# Calliope_mini_rev2_1.net
KiCad netlist of a schematic drawn in EAGLE
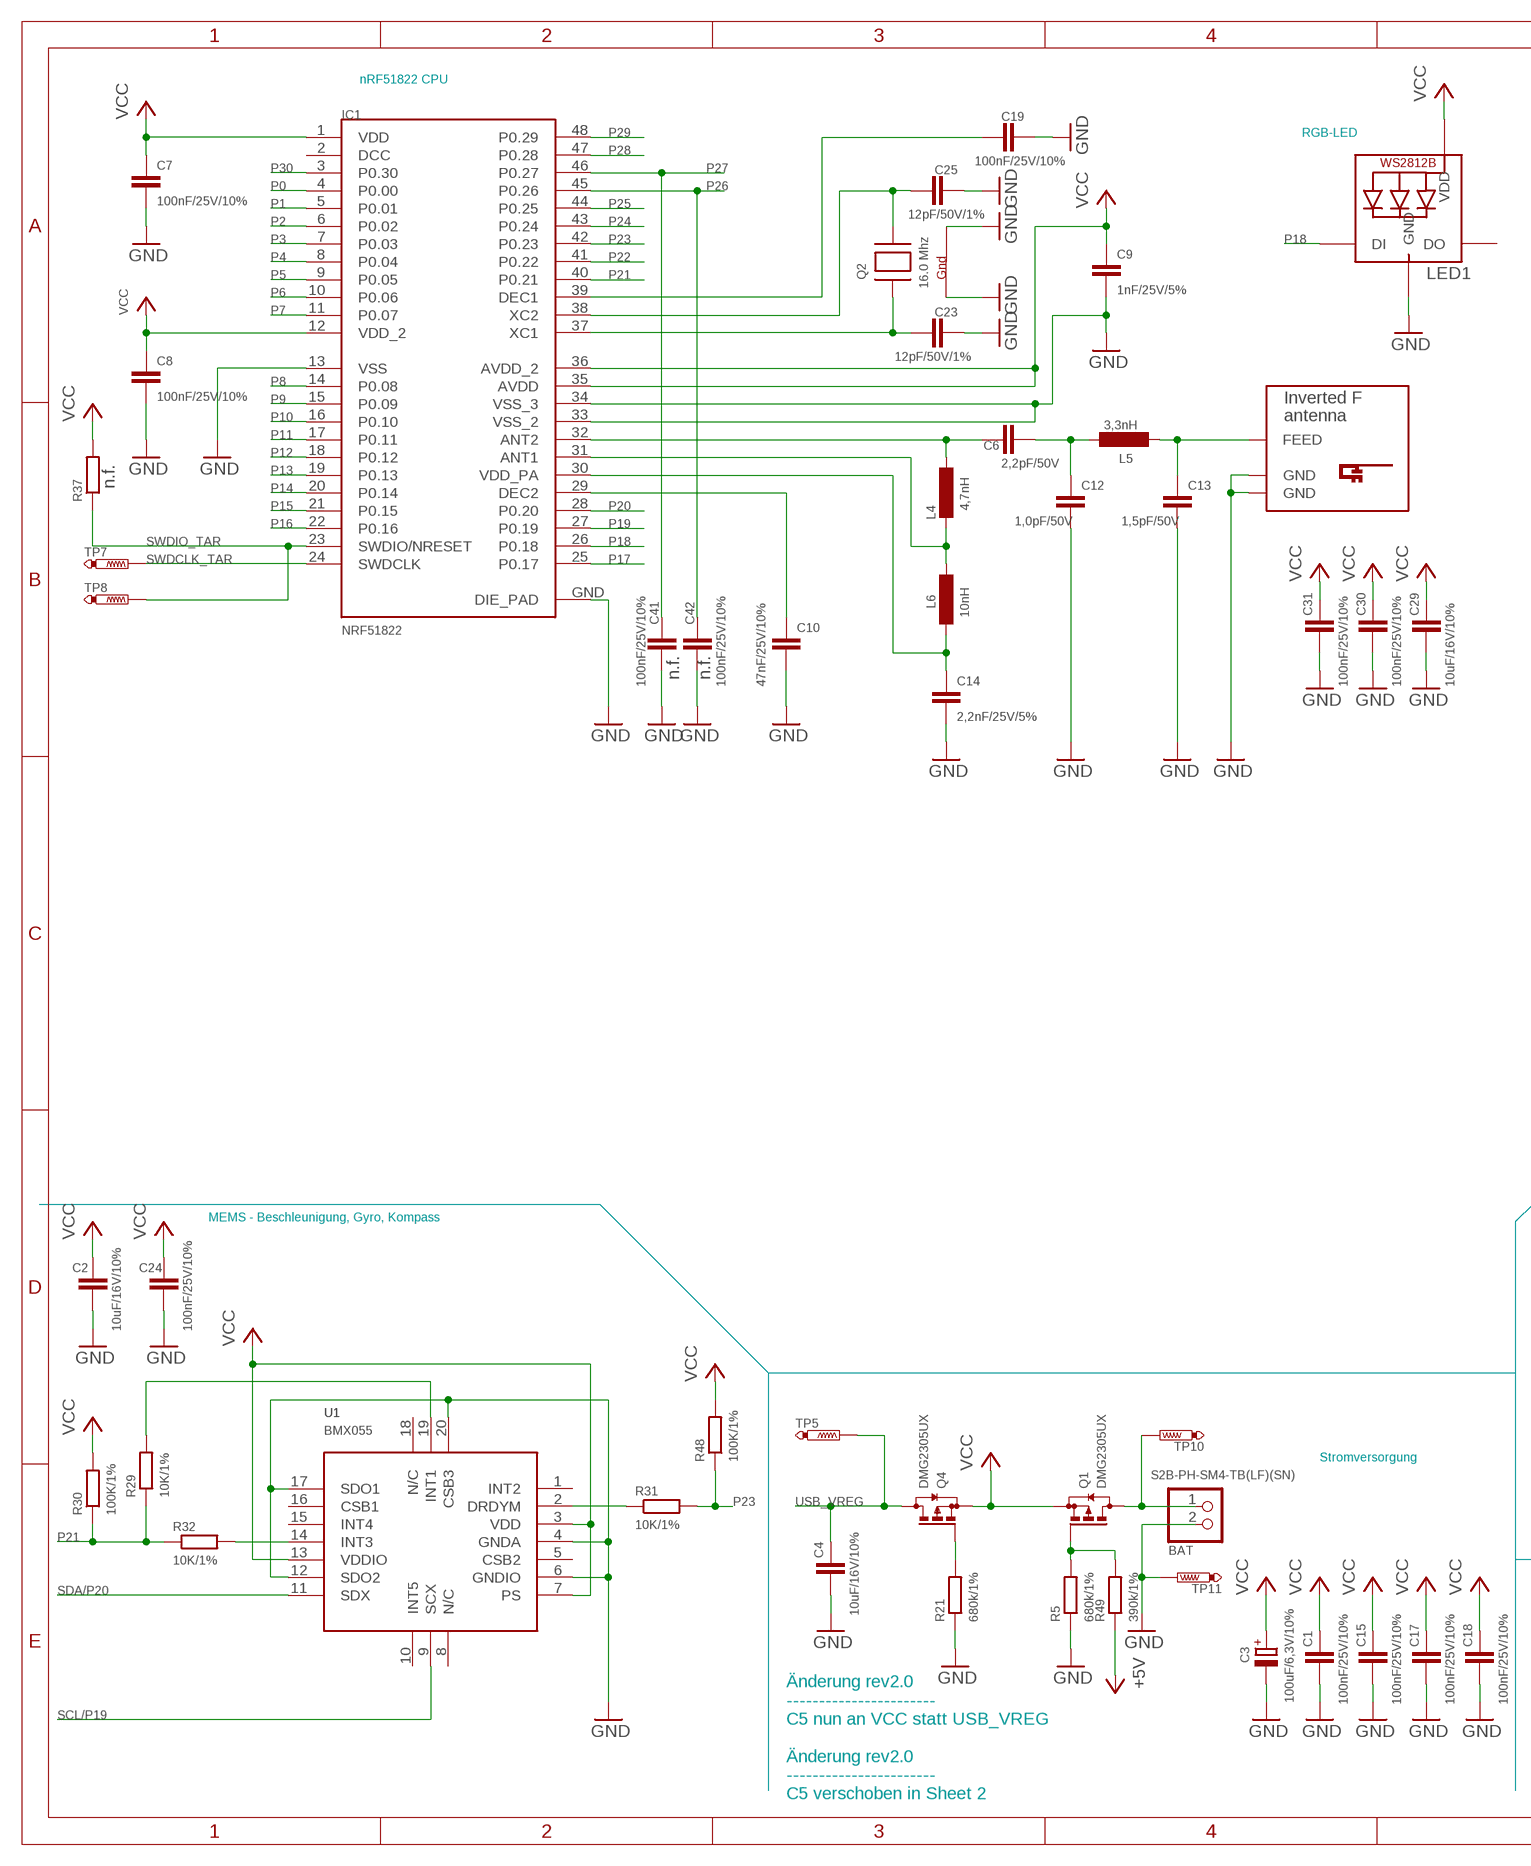
[diagram p0: schematic, sheet 1, part 1 of 2]
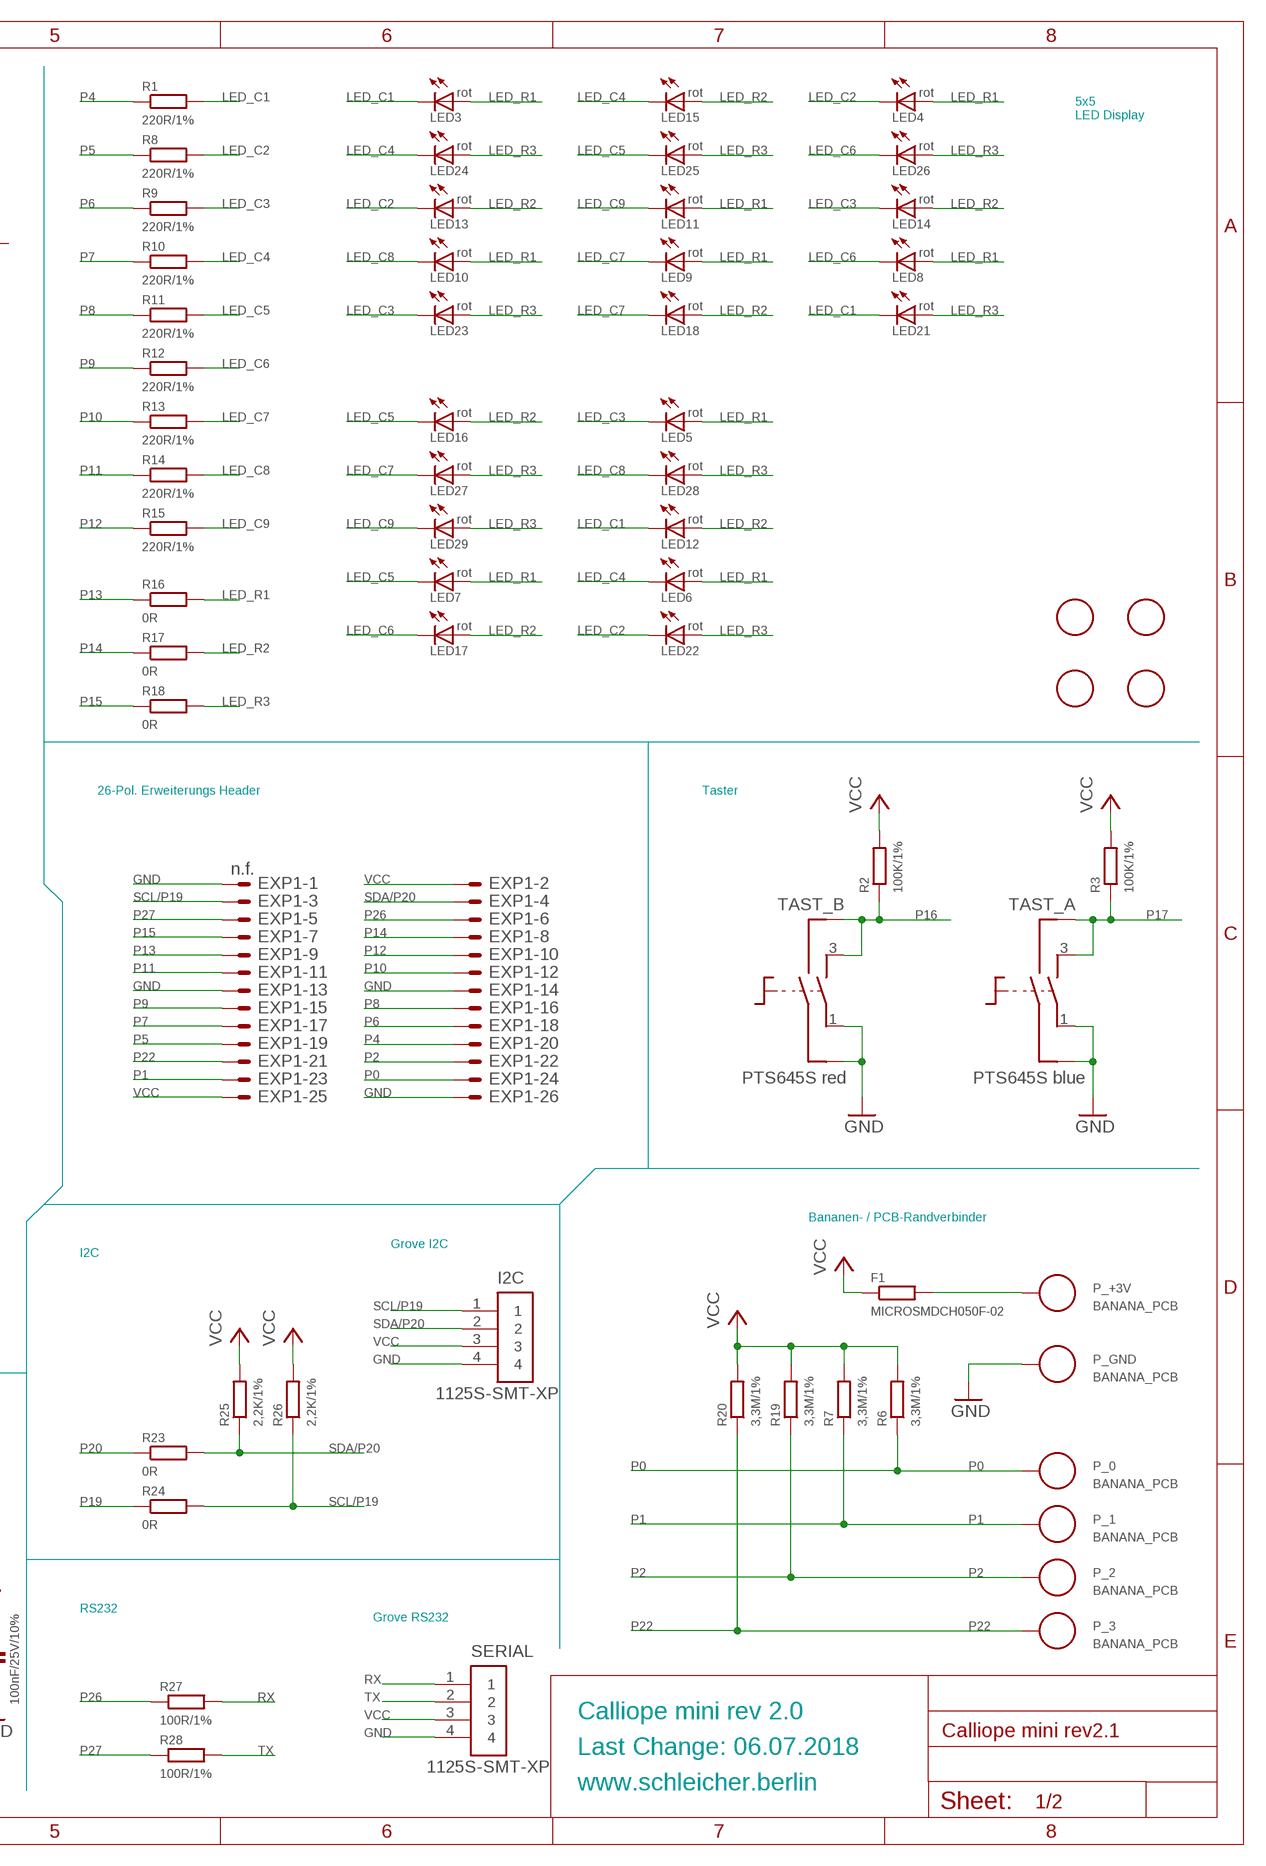
[diagram p1: schematic, sheet 1, part 2 of 2]
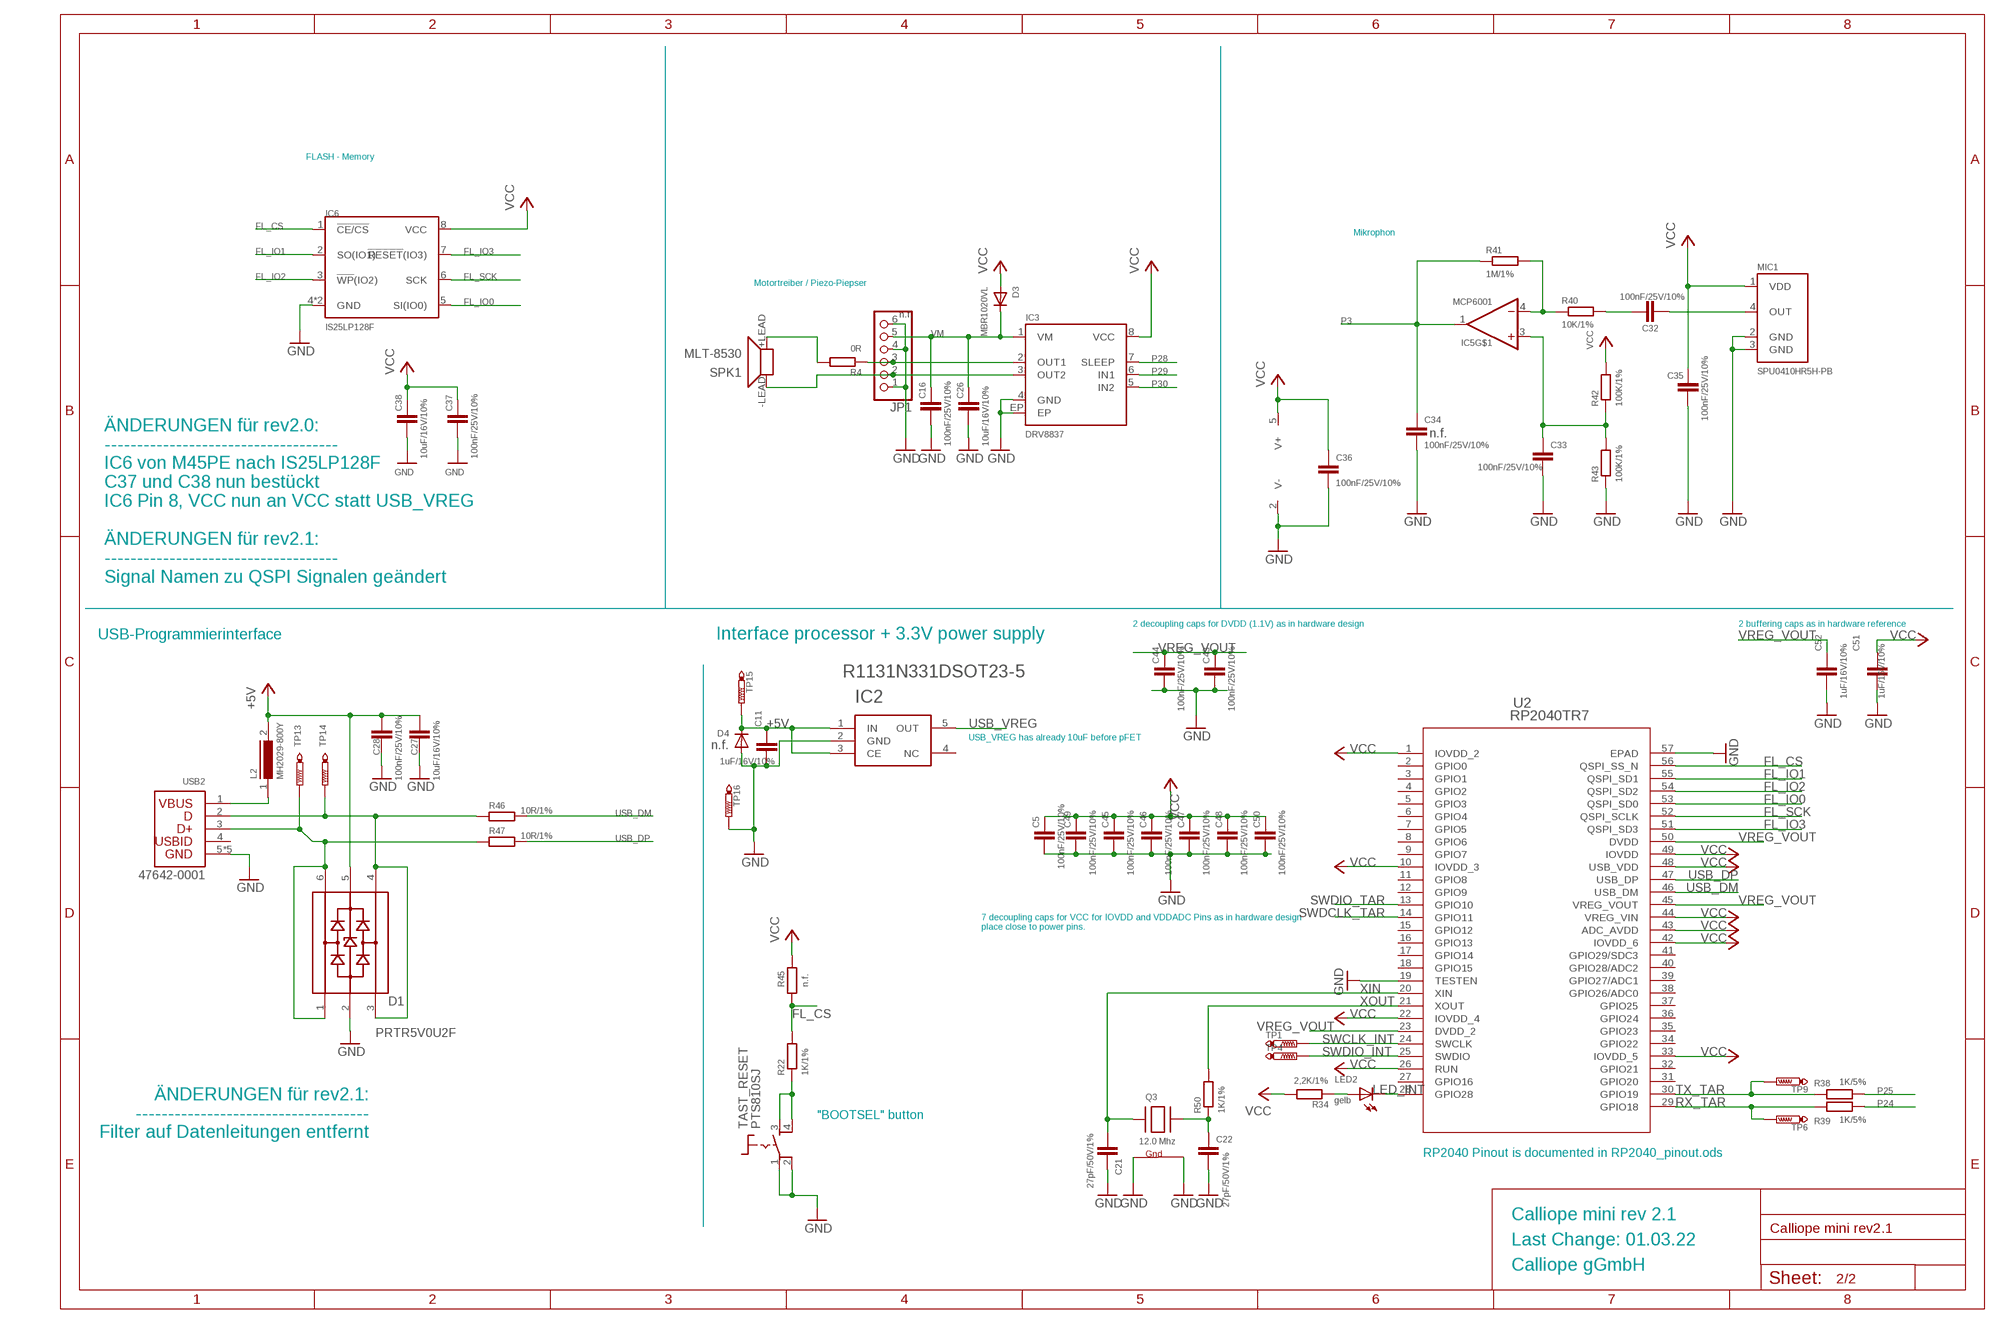
[diagram p2: schematic, sheet 2]

(export (version "E")
  (design (tool "Eeschema 10.0.6"))
  (components
    (comp (ref "C5")
      (value "100nF/25V/10%")
      (footprint "eagle-import:0402")
      (libsource (lib "eagle-import") (part "C-EU0402"))
    )
    (comp (ref "C11")
      (value "1uF/16V/10%")
      (footprint "eagle-import:0402")
      (libsource (lib "eagle-import") (part "rcl_334_C-EU0402"))
    )
    (comp (ref "C16")
      (value "100nF/25V/10%")
      (footprint "eagle-import:0402")
      (libsource (lib "eagle-import") (part "C-EU0402"))
    )
    (comp (ref "C21")
      (value "27pF/50V/1%")
      (footprint "eagle-import:0402")
      (libsource (lib "eagle-import") (part "C-EU0402"))
    )
    (comp (ref "C22")
      (value "27pF/50V/1%")
      (footprint "eagle-import:0402")
      (libsource (lib "eagle-import") (part "C-EU0402"))
    )
    (comp (ref "C26")
      (value "10uF/16V/10%")
      (footprint "eagle-import:0402")
      (libsource (lib "eagle-import") (part "rcl_334_C-EU0402"))
    )
    (comp (ref "C27")
      (value "10uF/16V/10%")
      (footprint "eagle-import:0402")
      (libsource (lib "eagle-import") (part "rcl_334_C-EU0402"))
    )
    (comp (ref "C28")
      (value "100nF/25V/10%")
      (footprint "eagle-import:0402")
      (libsource (lib "eagle-import") (part "C-EU0402"))
    )
    (comp (ref "C32")
      (value "100nF/25V/10%")
      (footprint "eagle-import:0402")
      (libsource (lib "eagle-import") (part "C-EU0402"))
    )
    (comp (ref "C33")
      (value "100nF/25V/10%")
      (footprint "eagle-import:0402")
      (libsource (lib "eagle-import") (part "C-EU0402"))
    )
    (comp (ref "C34")
      (value "100nF/25V/10%")
      (footprint "eagle-import:0402")
      (fields (field (name "MOUNTING") "n.f."))
      (libsource (lib "eagle-import") (part "C-EU0402"))
    )
    (comp (ref "C35")
      (value "100nF/25V/10%")
      (footprint "eagle-import:0402")
      (libsource (lib "eagle-import") (part "C-EU0402"))
    )
    (comp (ref "C36")
      (value "100nF/25V/10%")
      (footprint "eagle-import:0402")
      (libsource (lib "eagle-import") (part "C-EU0402"))
    )
    (comp (ref "C37")
      (value "100nF/25V/10%")
      (footprint "eagle-import:0402")
      (libsource (lib "eagle-import") (part "C-EU0402"))
    )
    (comp (ref "C38")
      (value "10uF/16V/10%")
      (footprint "eagle-import:0402")
      (libsource (lib "eagle-import") (part "rcl_334_C-EU0402"))
    )
    (comp (ref "C43")
      (value "100nF/25V/10%")
      (footprint "eagle-import:0402")
      (libsource (lib "eagle-import") (part "C-EU0402"))
    )
    (comp (ref "C44")
      (value "100nF/25V/10%")
      (footprint "eagle-import:0402")
      (libsource (lib "eagle-import") (part "C-EU0402"))
    )
    (comp (ref "C45")
      (value "100nF/25V/10%")
      (footprint "eagle-import:0402")
      (libsource (lib "eagle-import") (part "C-EU0402"))
    )
    (comp (ref "C46")
      (value "100nF/25V/10%")
      (footprint "eagle-import:0402")
      (libsource (lib "eagle-import") (part "C-EU0402"))
    )
    (comp (ref "C47")
      (value "100nF/25V/10%")
      (footprint "eagle-import:0402")
      (libsource (lib "eagle-import") (part "C-EU0402"))
    )
    (comp (ref "C48")
      (value "100nF/25V/10%")
      (footprint "eagle-import:0402")
      (libsource (lib "eagle-import") (part "C-EU0402"))
    )
    (comp (ref "C49")
      (value "100nF/25V/10%")
      (footprint "eagle-import:0402")
      (libsource (lib "eagle-import") (part "C-EU0402"))
    )
    (comp (ref "C50")
      (value "100nF/25V/10%")
      (footprint "eagle-import:0402")
      (libsource (lib "eagle-import") (part "C-EU0402"))
    )
    (comp (ref "C51")
      (value "1uF/16V/10%")
      (footprint "eagle-import:0402")
      (libsource (lib "eagle-import") (part "rcl_334_C-EU0402"))
    )
    (comp (ref "C52")
      (value "1uF/16V/10%")
      (footprint "eagle-import:0402")
      (libsource (lib "eagle-import") (part "rcl_334_C-EU0402"))
    )
    (comp (ref "D1")
      (value "PRTR5V0U2F")
      (footprint "eagle-import:SOT886")
      (libsource (lib "eagle-import") (part "PRTR5V0U2F"))
    )
    (comp (ref "D3")
      (value "MBR1020VL")
      (footprint "eagle-import:SOD-123FL")
      (libsource (lib "eagle-import") (part "DIODE_SOD-123FL"))
    )
    (comp (ref "D4")
      (value "DIODE-SOD323-R")
      (footprint "eagle-import:SOD323-R")
      (fields (field (name "MOUNTING") "n.f."))
      (libsource (lib "eagle-import") (part "DIODE-SOD323-R"))
    )
    (comp (ref "IC2")
      (value "R1131N331DSOT23-5")
      (footprint "eagle-import:SOT23-5")
      (libsource (lib "eagle-import") (part "R1131N331DSOT23-5"))
    )
    (comp (ref "IC3")
      (value "DRV8837")
      (footprint "eagle-import:WSON8")
      (libsource (lib "eagle-import") (part "DRV8837"))
    )
    (comp (ref "IC5")
      (value "MCP6001")
      (footprint "eagle-import:SOT23-5")
      (libsource (lib "eagle-import") (part "OPAMP_SINGLESOT23-5"))
    )
    (comp (ref "IC6")
      (value "IS25LP128F")
      (footprint "eagle-import:VQFN8_6X5")
      (libsource (lib "eagle-import") (part "IS25LP128F"))
    )
    (comp (ref "JP1")
      (value "PINHD-1X6-OFF")
      (footprint "eagle-import:1X06-OFF")
      (libsource (lib "eagle-import") (part "PINHD-1X6-OFF"))
    )
    (comp (ref "L2")
      (value "MH2029-800Y")
      (footprint "eagle-import:FERRIT_0805")
      (fields (field (name "TOLERANCE") "+-25%"))
      (libsource (lib "eagle-import") (part "MH2029-Y800"))
    )
    (comp (ref "LED2")
      (value "gelb")
      (footprint "eagle-import:CHIPLED_0603")
      (libsource (lib "eagle-import") (part "LEDCHIPLED_0603"))
    )
    (comp (ref "MIC1")
      (value "SPU0410HR5H-PB")
      (footprint "eagle-import:SPU0410HR5H-PB")
      (libsource (lib "eagle-import") (part "SPU0410HR5H-PB"))
    )
    (comp (ref "Q3")
      (value "12.0 Mhz")
      (footprint "eagle-import:NX3225")
      (libsource (lib "eagle-import") (part "XTAL-4-3225"))
    )
    (comp (ref "R4")
      (value "0R")
      (footprint "eagle-import:0402")
      (libsource (lib "eagle-import") (part "R-EU_0402"))
    )
    (comp (ref "R22")
      (value "1K/1%")
      (footprint "eagle-import:0402")
      (libsource (lib "eagle-import") (part "R-EU_0402"))
    )
    (comp (ref "R34")
      (value "2,2K/1%")
      (footprint "eagle-import:0402")
      (libsource (lib "eagle-import") (part "R-EU_0402"))
    )
    (comp (ref "R38")
      (value "1K/5%")
      (footprint "eagle-import:0402")
      (libsource (lib "eagle-import") (part "R-EU_0402"))
    )
    (comp (ref "R39")
      (value "1K/5%")
      (footprint "eagle-import:0402")
      (libsource (lib "eagle-import") (part "R-EU_0402"))
    )
    (comp (ref "R40")
      (value "10K/1%")
      (footprint "eagle-import:0402")
      (libsource (lib "eagle-import") (part "R-EU_0402"))
    )
    (comp (ref "R41")
      (value "1M/1%")
      (footprint "eagle-import:0402")
      (libsource (lib "eagle-import") (part "R-EU_0402"))
    )
    (comp (ref "R42")
      (value "100K/1%")
      (footprint "eagle-import:0402")
      (libsource (lib "eagle-import") (part "R-EU_0402"))
    )
    (comp (ref "R43")
      (value "100K/1%")
      (footprint "eagle-import:0402")
      (libsource (lib "eagle-import") (part "R-EU_0402"))
    )
    (comp (ref "R45")
      (value "n.f.")
      (footprint "eagle-import:0402")
      (libsource (lib "eagle-import") (part "R-EU_0402"))
    )
    (comp (ref "R46")
      (value "10R/1%")
      (footprint "eagle-import:R0402")
      (libsource (lib "eagle-import") (part "rcl_334_R-EU_R0402"))
    )
    (comp (ref "R47")
      (value "10R/1%")
      (footprint "eagle-import:R0402")
      (libsource (lib "eagle-import") (part "rcl_334_R-EU_R0402"))
    )
    (comp (ref "R50")
      (value "1K/1%")
      (footprint "eagle-import:0402")
      (libsource (lib "eagle-import") (part "R-EU_0402"))
    )
    (comp (ref "SPK1")
      (value "MLT-8530")
      (footprint "eagle-import:MLT-8530")
      (libsource (lib "eagle-import") (part "MLT-8530"))
    )
    (comp (ref "TAST_RESET")
      (value "PTS810SJ")
      (footprint "eagle-import:PTS810")
      (libsource (lib "eagle-import") (part "PTS810SJ"))
    )
    (comp (ref "TP1")
      (value "PTR1B1,27")
      (footprint "eagle-import:B1,27")
      (libsource (lib "eagle-import") (part "PTR1B1,27"))
    )
    (comp (ref "TP4")
      (value "PTR1B1,27")
      (footprint "eagle-import:B1,27")
      (libsource (lib "eagle-import") (part "PTR1B1,27"))
    )
    (comp (ref "TP6")
      (value "PTR1B1,27")
      (footprint "eagle-import:B1,27")
      (libsource (lib "eagle-import") (part "PTR1B1,27"))
    )
    (comp (ref "TP9")
      (value "PTR1B1,27")
      (footprint "eagle-import:B1,27")
      (libsource (lib "eagle-import") (part "PTR1B1,27"))
    )
    (comp (ref "TP13")
      (value "PTR1B1,27")
      (footprint "eagle-import:B1,27")
      (libsource (lib "eagle-import") (part "PTR1B1,27"))
    )
    (comp (ref "TP14")
      (value "PTR1B1,27")
      (footprint "eagle-import:B1,27")
      (libsource (lib "eagle-import") (part "PTR1B1,27"))
    )
    (comp (ref "TP15")
      (value "PTR1B1,27")
      (footprint "eagle-import:B1,27")
      (libsource (lib "eagle-import") (part "PTR1B1,27"))
    )
    (comp (ref "TP16")
      (value "PTR1B1,27")
      (footprint "eagle-import:B1,27")
      (libsource (lib "eagle-import") (part "PTR1B1,27"))
    )
    (comp (ref "U2")
      (value "RP2040TR7")
      (footprint "eagle-import:RP2040TR7_RPI")
      (fields (field (name "COPYRIGHT") "Copyright (C) 2022 Ultra Librarian. All rights reserved."))
      (libsource (lib "eagle-import") (part "RP2040TR7"))
    )
    (comp (ref "USB2")
      (value "47642-0001")
      (footprint "eagle-import:47642-0001")
      (libsource (lib "eagle-import") (part "47642-0001"))
    )
    (comp (ref "BAT")
      (value "S2B-PH-SM4-TB(LF)(SN)")
      (footprint "eagle-import:JST-PH-2-SMT-RA")
      (libsource (lib "eagle-import") (part "JST_2PIN-SMT-RA"))
    )
    (comp (ref "C1")
      (value "100nF/25V/10%")
      (footprint "eagle-import:0402")
      (libsource (lib "eagle-import") (part "C-EU0402"))
    )
    (comp (ref "C2")
      (value "10uF/16V/10%")
      (footprint "eagle-import:0402")
      (libsource (lib "eagle-import") (part "rcl_334_C-EU0402"))
    )
    (comp (ref "C3")
      (value "100uF/6,3V/10%")
      (footprint "eagle-import:D_7343-31R")
      (libsource (lib "eagle-import") (part "CPOL-EUD/7343-31R"))
    )
    (comp (ref "C4")
      (value "10uF/16V/10%")
      (footprint "eagle-import:0402")
      (libsource (lib "eagle-import") (part "rcl_334_C-EU0402"))
    )
    (comp (ref "C6")
      (value "2,2pF/50V")
      (footprint "eagle-import:0402")
      (libsource (lib "eagle-import") (part "C-EU0402"))
    )
    (comp (ref "C7")
      (value "100nF/25V/10%")
      (footprint "eagle-import:0402")
      (libsource (lib "eagle-import") (part "C-EU0402"))
    )
    (comp (ref "C8")
      (value "100nF/25V/10%")
      (footprint "eagle-import:0402")
      (libsource (lib "eagle-import") (part "C-EU0402"))
    )
    (comp (ref "C9")
      (value "1nF/25V/5%")
      (footprint "eagle-import:0402")
      (libsource (lib "eagle-import") (part "C-EU0402"))
    )
    (comp (ref "C10")
      (value "47nF/25V/10%")
      (footprint "eagle-import:0402")
      (libsource (lib "eagle-import") (part "C-EU0402"))
    )
    (comp (ref "C12")
      (value "1,0pF/50V")
      (footprint "eagle-import:0402")
      (libsource (lib "eagle-import") (part "C-EU0402"))
    )
    (comp (ref "C13")
      (value "1,5pF/50V")
      (footprint "eagle-import:0402")
      (libsource (lib "eagle-import") (part "C-EU0402"))
    )
    (comp (ref "C14")
      (value "2,2nF/25V/5%")
      (footprint "eagle-import:0402")
      (libsource (lib "eagle-import") (part "C-EU0402"))
    )
    (comp (ref "C15")
      (value "100nF/25V/10%")
      (footprint "eagle-import:0402")
      (libsource (lib "eagle-import") (part "C-EU0402"))
    )
    (comp (ref "C17")
      (value "100nF/25V/10%")
      (footprint "eagle-import:0402")
      (libsource (lib "eagle-import") (part "C-EU0402"))
    )
    (comp (ref "C18")
      (value "100nF/25V/10%")
      (footprint "eagle-import:0402")
      (libsource (lib "eagle-import") (part "C-EU0402"))
    )
    (comp (ref "C19")
      (value "100nF/25V/10%")
      (footprint "eagle-import:0402")
      (libsource (lib "eagle-import") (part "C-EU0402"))
    )
    (comp (ref "C23")
      (value "12pF/50V/1%")
      (footprint "eagle-import:0402")
      (libsource (lib "eagle-import") (part "C-EU0402"))
    )
    (comp (ref "C24")
      (value "100nF/25V/10%")
      (footprint "eagle-import:0402")
      (libsource (lib "eagle-import") (part "C-EU0402"))
    )
    (comp (ref "C25")
      (value "12pF/50V/1%")
      (footprint "eagle-import:0402")
      (libsource (lib "eagle-import") (part "C-EU0402"))
    )
    (comp (ref "C29")
      (value "10uF/16V/10%")
      (footprint "eagle-import:0402")
      (libsource (lib "eagle-import") (part "rcl_334_C-EU0402"))
    )
    (comp (ref "C30")
      (value "100nF/25V/10%")
      (footprint "eagle-import:0402")
      (libsource (lib "eagle-import") (part "C-EU0402"))
    )
    (comp (ref "C31")
      (value "100nF/25V/10%")
      (footprint "eagle-import:0402")
      (libsource (lib "eagle-import") (part "C-EU0402"))
    )
    (comp (ref "C41")
      (value "100nF/25V/10%")
      (footprint "eagle-import:0402")
      (fields (field (name "MOUNTING") "n.f."))
      (libsource (lib "eagle-import") (part "C-EU0402"))
    )
    (comp (ref "C42")
      (value "100nF/25V/10%")
      (footprint "eagle-import:0402")
      (fields (field (name "MOUNTING") "n.f."))
      (libsource (lib "eagle-import") (part "C-EU0402"))
    )
    (comp (ref "EXP1")
      (value "ML26E")
      (footprint "eagle-import:ML26")
      (fields (field (name "MOUNTING") "n.f."))
      (libsource (lib "eagle-import") (part "ML26?E"))
    )
    (comp (ref "F1")
      (value "MICROSMDCH050F-02")
      (footprint "eagle-import:R1210")
      (libsource (lib "eagle-import") (part "R-EU_R1210"))
    )
    (comp (ref "I2C")
      (value "1125S-SMT-XP")
      (footprint "eagle-import:1125S-SMT-XP")
      (libsource (lib "eagle-import") (part "1125-SMT-XPS"))
    )
    (comp (ref "IC1")
      (value "NRF51822")
      (footprint "eagle-import:QFN48")
      (libsource (lib "eagle-import") (part "NRF51822"))
    )
    (comp (ref "L4")
      (value "4,7nH")
      (footprint "eagle-import:0402")
      (libsource (lib "eagle-import") (part "L-EU0402"))
    )
    (comp (ref "L5")
      (value "3,3nH")
      (footprint "eagle-import:0402")
      (libsource (lib "eagle-import") (part "L-EU0402"))
    )
    (comp (ref "L6")
      (value "10nH")
      (footprint "eagle-import:0402")
      (libsource (lib "eagle-import") (part "L-EU0402"))
    )
    (comp (ref "LED1")
      (value "SK6812MINI")
      (footprint "eagle-import:LED3535")
      (libsource (lib "eagle-import") (part "WS2812B3535"))
    )
    (comp (ref "LED3")
      (value "rot")
      (footprint "eagle-import:CHIPLED_0603")
      (libsource (lib "eagle-import") (part "LEDCHIPLED_0603"))
    )
    (comp (ref "LED4")
      (value "rot")
      (footprint "eagle-import:CHIPLED_0603")
      (libsource (lib "eagle-import") (part "LEDCHIPLED_0603"))
    )
    (comp (ref "LED5")
      (value "rot")
      (footprint "eagle-import:CHIPLED_0603")
      (libsource (lib "eagle-import") (part "LEDCHIPLED_0603"))
    )
    (comp (ref "LED6")
      (value "rot")
      (footprint "eagle-import:CHIPLED_0603")
      (libsource (lib "eagle-import") (part "LEDCHIPLED_0603"))
    )
    (comp (ref "LED7")
      (value "rot")
      (footprint "eagle-import:CHIPLED_0603")
      (libsource (lib "eagle-import") (part "LEDCHIPLED_0603"))
    )
    (comp (ref "LED8")
      (value "rot")
      (footprint "eagle-import:CHIPLED_0603")
      (libsource (lib "eagle-import") (part "LEDCHIPLED_0603"))
    )
    (comp (ref "LED9")
      (value "rot")
      (footprint "eagle-import:CHIPLED_0603")
      (libsource (lib "eagle-import") (part "LEDCHIPLED_0603"))
    )
    (comp (ref "LED10")
      (value "rot")
      (footprint "eagle-import:CHIPLED_0603")
      (libsource (lib "eagle-import") (part "LEDCHIPLED_0603"))
    )
    (comp (ref "LED11")
      (value "rot")
      (footprint "eagle-import:CHIPLED_0603")
      (libsource (lib "eagle-import") (part "LEDCHIPLED_0603"))
    )
    (comp (ref "LED12")
      (value "rot")
      (footprint "eagle-import:CHIPLED_0603")
      (libsource (lib "eagle-import") (part "LEDCHIPLED_0603"))
    )
    (comp (ref "LED13")
      (value "rot")
      (footprint "eagle-import:CHIPLED_0603")
      (libsource (lib "eagle-import") (part "LEDCHIPLED_0603"))
    )
    (comp (ref "LED14")
      (value "rot")
      (footprint "eagle-import:CHIPLED_0603")
      (libsource (lib "eagle-import") (part "LEDCHIPLED_0603"))
    )
    (comp (ref "LED15")
      (value "rot")
      (footprint "eagle-import:CHIPLED_0603")
      (libsource (lib "eagle-import") (part "LEDCHIPLED_0603"))
    )
    (comp (ref "LED16")
      (value "rot")
      (footprint "eagle-import:CHIPLED_0603")
      (libsource (lib "eagle-import") (part "LEDCHIPLED_0603"))
    )
    (comp (ref "LED17")
      (value "rot")
      (footprint "eagle-import:CHIPLED_0603")
      (libsource (lib "eagle-import") (part "LEDCHIPLED_0603"))
    )
    (comp (ref "LED18")
      (value "rot")
      (footprint "eagle-import:CHIPLED_0603")
      (libsource (lib "eagle-import") (part "LEDCHIPLED_0603"))
    )
    (comp (ref "LED21")
      (value "rot")
      (footprint "eagle-import:CHIPLED_0603")
      (libsource (lib "eagle-import") (part "LEDCHIPLED_0603"))
    )
    (comp (ref "LED22")
      (value "rot")
      (footprint "eagle-import:CHIPLED_0603")
      (libsource (lib "eagle-import") (part "LEDCHIPLED_0603"))
    )
    (comp (ref "LED23")
      (value "rot")
      (footprint "eagle-import:CHIPLED_0603")
      (libsource (lib "eagle-import") (part "LEDCHIPLED_0603"))
    )
    (comp (ref "LED24")
      (value "rot")
      (footprint "eagle-import:CHIPLED_0603")
      (libsource (lib "eagle-import") (part "LEDCHIPLED_0603"))
    )
    (comp (ref "LED25")
      (value "rot")
      (footprint "eagle-import:CHIPLED_0603")
      (libsource (lib "eagle-import") (part "LEDCHIPLED_0603"))
    )
    (comp (ref "LED26")
      (value "rot")
      (footprint "eagle-import:CHIPLED_0603")
      (libsource (lib "eagle-import") (part "LEDCHIPLED_0603"))
    )
    (comp (ref "LED27")
      (value "rot")
      (footprint "eagle-import:CHIPLED_0603")
      (libsource (lib "eagle-import") (part "LEDCHIPLED_0603"))
    )
    (comp (ref "LED28")
      (value "rot")
      (footprint "eagle-import:CHIPLED_0603")
      (libsource (lib "eagle-import") (part "LEDCHIPLED_0603"))
    )
    (comp (ref "LED29")
      (value "rot")
      (footprint "eagle-import:CHIPLED_0603")
      (libsource (lib "eagle-import") (part "LEDCHIPLED_0603"))
    )
    (comp (ref "P_+3V")
      (value "BANANA_PCB")
      (footprint "eagle-import:BANANA_REC")
      (libsource (lib "eagle-import") (part "BANANA_PCB"))
    )
    (comp (ref "P_0")
      (value "BANANA_PCB")
      (footprint "eagle-import:BANANA_REC")
      (libsource (lib "eagle-import") (part "BANANA_PCB"))
    )
    (comp (ref "P_1")
      (value "BANANA_PCB")
      (footprint "eagle-import:BANANA_REC")
      (libsource (lib "eagle-import") (part "BANANA_PCB"))
    )
    (comp (ref "P_2")
      (value "BANANA_PCB")
      (footprint "eagle-import:BANANA_REC")
      (libsource (lib "eagle-import") (part "BANANA_PCB"))
    )
    (comp (ref "P_3")
      (value "BANANA_PCB")
      (footprint "eagle-import:BANANA_REC")
      (libsource (lib "eagle-import") (part "BANANA_PCB"))
    )
    (comp (ref "P_GND")
      (value "BANANA_PCB")
      (footprint "eagle-import:BANANA_REC")
      (libsource (lib "eagle-import") (part "BANANA_PCB"))
    )
    (comp (ref "Q1")
      (value "DMG2305UX")
      (footprint "eagle-import:SOT23")
      (libsource (lib "eagle-import") (part "BSS84"))
    )
    (comp (ref "Q2")
      (value "16.0 Mhz")
      (footprint "eagle-import:NX3225")
      (libsource (lib "eagle-import") (part "XTAL-4-3225"))
    )
    (comp (ref "Q4")
      (value "DMG2305UX")
      (footprint "eagle-import:SOT23")
      (libsource (lib "eagle-import") (part "BSS84"))
    )
    (comp (ref "R1")
      (value "220R/1%")
      (footprint "eagle-import:0402")
      (libsource (lib "eagle-import") (part "R-EU_0402"))
    )
    (comp (ref "R2")
      (value "100K/1%")
      (footprint "eagle-import:0402")
      (libsource (lib "eagle-import") (part "R-EU_0402"))
    )
    (comp (ref "R3")
      (value "100K/1%")
      (footprint "eagle-import:0402")
      (libsource (lib "eagle-import") (part "R-EU_0402"))
    )
    (comp (ref "R5")
      (value "680k/1%")
      (footprint "eagle-import:0402")
      (libsource (lib "eagle-import") (part "R-EU_0402"))
    )
    (comp (ref "R6")
      (value "3,3M/1%")
      (footprint "eagle-import:0402")
      (libsource (lib "eagle-import") (part "R-EU_0402"))
    )
    (comp (ref "R7")
      (value "3,3M/1%")
      (footprint "eagle-import:0402")
      (libsource (lib "eagle-import") (part "R-EU_0402"))
    )
    (comp (ref "R8")
      (value "220R/1%")
      (footprint "eagle-import:0402")
      (libsource (lib "eagle-import") (part "R-EU_0402"))
    )
    (comp (ref "R9")
      (value "220R/1%")
      (footprint "eagle-import:0402")
      (libsource (lib "eagle-import") (part "R-EU_0402"))
    )
    (comp (ref "R10")
      (value "220R/1%")
      (footprint "eagle-import:0402")
      (libsource (lib "eagle-import") (part "R-EU_0402"))
    )
    (comp (ref "R11")
      (value "220R/1%")
      (footprint "eagle-import:0402")
      (libsource (lib "eagle-import") (part "R-EU_0402"))
    )
    (comp (ref "R12")
      (value "220R/1%")
      (footprint "eagle-import:0402")
      (libsource (lib "eagle-import") (part "R-EU_0402"))
    )
    (comp (ref "R13")
      (value "220R/1%")
      (footprint "eagle-import:0402")
      (libsource (lib "eagle-import") (part "R-EU_0402"))
    )
    (comp (ref "R14")
      (value "220R/1%")
      (footprint "eagle-import:0402")
      (libsource (lib "eagle-import") (part "R-EU_0402"))
    )
    (comp (ref "R15")
      (value "220R/1%")
      (footprint "eagle-import:0402")
      (libsource (lib "eagle-import") (part "R-EU_0402"))
    )
    (comp (ref "R16")
      (value "0R")
      (footprint "eagle-import:0402")
      (libsource (lib "eagle-import") (part "R-EU_0402"))
    )
    (comp (ref "R17")
      (value "0R")
      (footprint "eagle-import:0402")
      (libsource (lib "eagle-import") (part "R-EU_0402"))
    )
    (comp (ref "R18")
      (value "0R")
      (footprint "eagle-import:0402")
      (libsource (lib "eagle-import") (part "R-EU_0402"))
    )
    (comp (ref "R19")
      (value "3,3M/1%")
      (footprint "eagle-import:0402")
      (libsource (lib "eagle-import") (part "R-EU_0402"))
    )
    (comp (ref "R20")
      (value "3,3M/1%")
      (footprint "eagle-import:0402")
      (libsource (lib "eagle-import") (part "R-EU_0402"))
    )
    (comp (ref "R21")
      (value "680k/1%")
      (footprint "eagle-import:0402")
      (libsource (lib "eagle-import") (part "R-EU_0402"))
    )
    (comp (ref "R23")
      (value "0R")
      (footprint "eagle-import:0402")
      (libsource (lib "eagle-import") (part "R-EU_0402"))
    )
    (comp (ref "R24")
      (value "0R")
      (footprint "eagle-import:0402")
      (libsource (lib "eagle-import") (part "R-EU_0402"))
    )
    (comp (ref "R25")
      (value "2,2K/1%")
      (footprint "eagle-import:0402")
      (libsource (lib "eagle-import") (part "R-EU_0402"))
    )
    (comp (ref "R26")
      (value "2,2K/1%")
      (footprint "eagle-import:0402")
      (libsource (lib "eagle-import") (part "R-EU_0402"))
    )
    (comp (ref "R27")
      (value "100R/1%")
      (footprint "eagle-import:0402")
      (libsource (lib "eagle-import") (part "R-EU_0402"))
    )
    (comp (ref "R28")
      (value "100R/1%")
      (footprint "eagle-import:0402")
      (libsource (lib "eagle-import") (part "R-EU_0402"))
    )
    (comp (ref "R29")
      (value "10K/1%")
      (footprint "eagle-import:0402")
      (libsource (lib "eagle-import") (part "R-EU_0402"))
    )
    (comp (ref "R30")
      (value "100K/1%")
      (footprint "eagle-import:0402")
      (libsource (lib "eagle-import") (part "R-EU_0402"))
    )
    (comp (ref "R31")
      (value "10K/1%")
      (footprint "eagle-import:0402")
      (libsource (lib "eagle-import") (part "R-EU_0402"))
    )
    (comp (ref "R32")
      (value "10K/1%")
      (footprint "eagle-import:0402")
      (libsource (lib "eagle-import") (part "R-EU_0402"))
    )
    (comp (ref "R37")
      (value "R-EU_0402")
      (footprint "eagle-import:0402")
      (fields (field (name "MOUNTING") "n.f."))
      (libsource (lib "eagle-import") (part "R-EU_0402"))
    )
    (comp (ref "R48")
      (value "100K/1%")
      (footprint "eagle-import:0402")
      (libsource (lib "eagle-import") (part "R-EU_0402"))
    )
    (comp (ref "R49")
      (value "390k/1%")
      (footprint "eagle-import:0402")
      (libsource (lib "eagle-import") (part "R-EU_0402"))
    )
    (comp (ref "SERIAL")
      (value "1125S-SMT-XP")
      (footprint "eagle-import:1125S-SMT-XP")
      (libsource (lib "eagle-import") (part "1125-SMT-XPS"))
    )
    (comp (ref "TAST_A")
      (value "PTS645S blue")
      (footprint "eagle-import:PTS645S")
      (libsource (lib "eagle-import") (part "PTS645S"))
    )
    (comp (ref "TAST_B")
      (value "PTS645S red")
      (footprint "eagle-import:PTS645S")
      (libsource (lib "eagle-import") (part "PTS645S"))
    )
    (comp (ref "TP5")
      (value "PTR1B1,27")
      (footprint "eagle-import:B1,27")
      (libsource (lib "eagle-import") (part "PTR1B1,27"))
    )
    (comp (ref "TP7")
      (value "PTR1B1,27")
      (footprint "eagle-import:B1,27")
      (libsource (lib "eagle-import") (part "PTR1B1,27"))
    )
    (comp (ref "TP8")
      (value "PTR1B1,27")
      (footprint "eagle-import:B1,27")
      (libsource (lib "eagle-import") (part "PTR1B1,27"))
    )
    (comp (ref "TP10")
      (value "PTR1B1,27")
      (footprint "eagle-import:B1,27")
      (libsource (lib "eagle-import") (part "PTR1B1,27"))
    )
    (comp (ref "TP11")
      (value "PTR1B1,27")
      (footprint "eagle-import:B1,27")
      (libsource (lib "eagle-import") (part "PTR1B1,27"))
    )
    (comp (ref "U$2")
      (value "INVERTED_F_ANTENNA")
      (footprint "eagle-import:DN0007+0_MIRROR")
      (libsource (lib "eagle-import") (part "INVERTED_F_ANTENNA"))
    )
    (comp (ref "U$5")
      (value "FIDUCIAL")
      (footprint "eagle-import:FIDUCIAL_1MM")
      (libsource (lib "eagle-import") (part "FIDUCIAL"))
    )
    (comp (ref "U$6")
      (value "FIDUCIAL")
      (footprint "eagle-import:FIDUCIAL_1MM")
      (libsource (lib "eagle-import") (part "FIDUCIAL"))
    )
    (comp (ref "U$7")
      (value "FIDUCIAL")
      (footprint "eagle-import:FIDUCIAL_1MM")
      (libsource (lib "eagle-import") (part "FIDUCIAL"))
    )
    (comp (ref "U$8")
      (value "FIDUCIAL")
      (footprint "eagle-import:FIDUCIAL_1MM")
      (libsource (lib "eagle-import") (part "FIDUCIAL"))
    )
    (comp (ref "U1")
      (value "BMX055")
      (footprint "eagle-import:BMX055")
      (libsource (lib "eagle-import") (part "BMX055"))
    )
  )
  (nets
    (net (code "1") (name "+5V") (class "Default")
      (node (ref "C11") (pin "1") (pinfunction "1_1") (pintype "passive"))
      (node (ref "C27") (pin "1") (pinfunction "1_1") (pintype "passive"))
      (node (ref "C28") (pin "1") (pinfunction "1_1") (pintype "passive"))
      (node (ref "D1") (pin "5") (pinfunction "5_5") (pintype "bidirectional"))
      (node (ref "D4") (pin "C") (pinfunction "C_C") (pintype "passive"))
      (node (ref "IC2") (pin "1") (pinfunction "IN_1") (pintype "input"))
      (node (ref "IC2") (pin "3") (pinfunction "CE_3") (pintype "input"))
      (node (ref "L2") (pin "2") (pinfunction "2_2") (pintype "passive"))
      (node (ref "R49") (pin "1") (pinfunction "1_1") (pintype "passive"))
      (node (ref "TP15") (pin "TP") (pinfunction "TP_TP") (pintype "input"))
    )
    (net (code "2") (name "FL_CS") (class "Default")
      (node (ref "IC6") (pin "1") (pinfunction "~{CE/CS}_1") (pintype "bidirectional"))
      (node (ref "R22") (pin "2") (pinfunction "2_2") (pintype "passive"))
      (node (ref "R45") (pin "1") (pinfunction "1_1") (pintype "passive"))
      (node (ref "U2") (pin "56") (pinfunction "QSPI_SS_N_56") (pintype "bidirectional"))
    )
    (net (code "3") (name "FL_IO0") (class "Default")
      (node (ref "IC6") (pin "5") (pinfunction "SI(IO0)_5") (pintype "bidirectional"))
      (node (ref "U2") (pin "53") (pinfunction "QSPI_SD0_53") (pintype "bidirectional"))
    )
    (net (code "4") (name "FL_IO1") (class "Default")
      (node (ref "IC6") (pin "2") (pinfunction "SO(IO1)_2") (pintype "bidirectional"))
      (node (ref "U2") (pin "55") (pinfunction "QSPI_SD1_55") (pintype "bidirectional"))
    )
    (net (code "5") (name "FL_IO2") (class "Default")
      (node (ref "IC6") (pin "3") (pinfunction "~{WP}(IO2)_3") (pintype "bidirectional"))
      (node (ref "U2") (pin "54") (pinfunction "QSPI_SD2_54") (pintype "bidirectional"))
    )
    (net (code "6") (name "FL_IO3") (class "Default")
      (node (ref "IC6") (pin "7") (pinfunction "~{RESET}(IO3)_7") (pintype "bidirectional"))
      (node (ref "U2") (pin "51") (pinfunction "QSPI_SD3_51") (pintype "bidirectional"))
    )
    (net (code "7") (name "FL_SCK") (class "Default")
      (node (ref "IC6") (pin "6") (pinfunction "SCK_6") (pintype "bidirectional"))
      (node (ref "U2") (pin "52") (pinfunction "QSPI_SCLK_52") (pintype "bidirectional"))
    )
    (net (code "8") (name "GND") (class "Default")
      (node (ref "BAT") (pin "2") (pinfunction "1_2") (pintype "passive"))
      (node (ref "C1") (pin "2") (pinfunction "2_2") (pintype "passive"))
      (node (ref "C10") (pin "2") (pinfunction "2_2") (pintype "passive"))
      (node (ref "C11") (pin "2") (pinfunction "2_2") (pintype "passive"))
      (node (ref "C12") (pin "2") (pinfunction "2_2") (pintype "passive"))
      (node (ref "C13") (pin "2") (pinfunction "2_2") (pintype "passive"))
      (node (ref "C14") (pin "2") (pinfunction "2_2") (pintype "passive"))
      (node (ref "C15") (pin "2") (pinfunction "2_2") (pintype "passive"))
      (node (ref "C16") (pin "2") (pinfunction "2_2") (pintype "passive"))
      (node (ref "C17") (pin "2") (pinfunction "2_2") (pintype "passive"))
      (node (ref "C18") (pin "2") (pinfunction "2_2") (pintype "passive"))
      (node (ref "C19") (pin "2") (pinfunction "2_2") (pintype "passive"))
      (node (ref "C2") (pin "2") (pinfunction "2_2") (pintype "passive"))
      (node (ref "C21") (pin "2") (pinfunction "2_2") (pintype "passive"))
      (node (ref "C22") (pin "2") (pinfunction "2_2") (pintype "passive"))
      (node (ref "C23") (pin "2") (pinfunction "2_2") (pintype "passive"))
      (node (ref "C24") (pin "2") (pinfunction "2_2") (pintype "passive"))
      (node (ref "C25") (pin "2") (pinfunction "2_2") (pintype "passive"))
      (node (ref "C26") (pin "2") (pinfunction "2_2") (pintype "passive"))
      (node (ref "C27") (pin "2") (pinfunction "2_2") (pintype "passive"))
      (node (ref "C28") (pin "2") (pinfunction "2_2") (pintype "passive"))
      (node (ref "C29") (pin "2") (pinfunction "2_2") (pintype "passive"))
      (node (ref "C3") (pin "-") (pinfunction "-_-") (pintype "passive"))
      (node (ref "C30") (pin "2") (pinfunction "2_2") (pintype "passive"))
      (node (ref "C31") (pin "2") (pinfunction "2_2") (pintype "passive"))
      (node (ref "C33") (pin "2") (pinfunction "2_2") (pintype "passive"))
      (node (ref "C34") (pin "2") (pinfunction "2_2") (pintype "passive"))
      (node (ref "C35") (pin "2") (pinfunction "2_2") (pintype "passive"))
      (node (ref "C36") (pin "2") (pinfunction "2_2") (pintype "passive"))
      (node (ref "C37") (pin "2") (pinfunction "2_2") (pintype "passive"))
      (node (ref "C38") (pin "2") (pinfunction "2_2") (pintype "passive"))
      (node (ref "C4") (pin "2") (pinfunction "2_2") (pintype "passive"))
      (node (ref "C41") (pin "2") (pinfunction "2_2") (pintype "passive"))
      (node (ref "C42") (pin "2") (pinfunction "2_2") (pintype "passive"))
      (node (ref "C43") (pin "2") (pinfunction "2_2") (pintype "passive"))
      (node (ref "C44") (pin "2") (pinfunction "2_2") (pintype "passive"))
      (node (ref "C45") (pin "2") (pinfunction "2_2") (pintype "passive"))
      (node (ref "C46") (pin "2") (pinfunction "2_2") (pintype "passive"))
      (node (ref "C47") (pin "2") (pinfunction "2_2") (pintype "passive"))
      (node (ref "C48") (pin "2") (pinfunction "2_2") (pintype "passive"))
      (node (ref "C49") (pin "2") (pinfunction "2_2") (pintype "passive"))
      (node (ref "C5") (pin "2") (pinfunction "2_2") (pintype "passive"))
      (node (ref "C50") (pin "2") (pinfunction "2_2") (pintype "passive"))
      (node (ref "C51") (pin "2") (pinfunction "2_2") (pintype "passive"))
      (node (ref "C52") (pin "2") (pinfunction "2_2") (pintype "passive"))
      (node (ref "C7") (pin "2") (pinfunction "2_2") (pintype "passive"))
      (node (ref "C8") (pin "2") (pinfunction "2_2") (pintype "passive"))
      (node (ref "C9") (pin "2") (pinfunction "2_2") (pintype "passive"))
      (node (ref "D1") (pin "2") (pinfunction "2_2") (pintype "bidirectional"))
      (node (ref "D4") (pin "A") (pinfunction "A_A") (pintype "passive"))
      (node (ref "EXP1") (pin "1") (pinfunction "S_1") (pintype "passive"))
      (node (ref "EXP1") (pin "13") (pinfunction "S_13") (pintype "passive"))
      (node (ref "EXP1") (pin "14") (pinfunction "S_14") (pintype "passive"))
      (node (ref "EXP1") (pin "26") (pinfunction "S_26") (pintype "passive"))
      (node (ref "I2C") (pin "4") (pinfunction "4_4") (pintype "bidirectional"))
      (node (ref "IC1") (pin "13") (pinfunction "VSS_13") (pintype "bidirectional"))
      (node (ref "IC1") (pin "33") (pinfunction "VSS_2_33") (pintype "bidirectional"))
      (node (ref "IC1") (pin "34") (pinfunction "VSS_3_34") (pintype "bidirectional"))
      (node (ref "IC1") (pin "GND") (pinfunction "DIE_PAD_GND") (pintype "bidirectional"))
      (node (ref "IC2") (pin "2") (pinfunction "GND_2") (pintype "input"))
      (node (ref "IC3") (pin "4") (pinfunction "GND_4") (pintype "bidirectional"))
      (node (ref "IC3") (pin "EP") (pinfunction "EP_EP") (pintype "bidirectional"))
      (node (ref "IC5") (pin "2") (pinfunction "V-_2") (pintype "power_in"))
      (node (ref "IC6") (pin "4") (pinfunction "GND_4") (pintype "bidirectional"))
      (node (ref "IC6") (pin "EP") (pinfunction "GND_EP") (pintype "bidirectional"))
      (node (ref "JP1") (pin "1") (pinfunction "1_1") (pintype "passive"))
      (node (ref "JP1") (pin "4") (pinfunction "4_4") (pintype "passive"))
      (node (ref "JP1") (pin "6") (pinfunction "6_6") (pintype "passive"))
      (node (ref "LED1") (pin "4") (pinfunction "GND_4") (pintype "power_in"))
      (node (ref "MIC1") (pin "2") (pinfunction "GND_2") (pintype "bidirectional"))
      (node (ref "MIC1") (pin "3") (pinfunction "GND_3") (pintype "bidirectional"))
      (node (ref "P_GND") (pin "1") (pinfunction "1_1") (pintype "bidirectional"))
      (node (ref "Q2") (pin "2") (pinfunction "G2_2") (pintype "power_in"))
      (node (ref "Q2") (pin "4") (pinfunction "G1_4") (pintype "power_in"))
      (node (ref "Q3") (pin "2") (pinfunction "G2_2") (pintype "power_in"))
      (node (ref "Q3") (pin "4") (pinfunction "G1_4") (pintype "power_in"))
      (node (ref "R21") (pin "1") (pinfunction "1_1") (pintype "passive"))
      (node (ref "R43") (pin "1") (pinfunction "1_1") (pintype "passive"))
      (node (ref "R5") (pin "1") (pinfunction "1_1") (pintype "passive"))
      (node (ref "SERIAL") (pin "4") (pinfunction "4_4") (pintype "bidirectional"))
      (node (ref "TAST_A") (pin "1") (pinfunction "P1_1") (pintype "passive"))
      (node (ref "TAST_A") (pin "2") (pinfunction "P2_2") (pintype "passive"))
      (node (ref "TAST_B") (pin "1") (pinfunction "P1_1") (pintype "passive"))
      (node (ref "TAST_B") (pin "2") (pinfunction "P2_2") (pintype "passive"))
      (node (ref "TAST_RESET") (pin "1") (pinfunction "P_1") (pintype "passive"))
      (node (ref "TAST_RESET") (pin "2") (pinfunction "P1_2") (pintype "passive"))
      (node (ref "TP11") (pin "TP") (pinfunction "TP_TP") (pintype "input"))
      (node (ref "TP16") (pin "TP") (pinfunction "TP_TP") (pintype "input"))
      (node (ref "U$2") (pin "GND") (pinfunction "GND_GND") (pintype "bidirectional"))
      (node (ref "U$2") (pin "GND@1") (pinfunction "GND_GND@1") (pintype "bidirectional"))
      (node (ref "U1") (pin "12") (pinfunction "SDO2_12") (pintype "bidirectional"))
      (node (ref "U1") (pin "17") (pinfunction "SDO1_17") (pintype "bidirectional"))
      (node (ref "U1") (pin "20") (pinfunction "CSB3_20") (pintype "bidirectional"))
      (node (ref "U1") (pin "4") (pinfunction "GNDA_4") (pintype "bidirectional"))
      (node (ref "U1") (pin "6") (pinfunction "GNDIO_6") (pintype "bidirectional"))
      (node (ref "U2") (pin "19") (pinfunction "TESTEN_19") (pintype "passive"))
      (node (ref "U2") (pin "57") (pinfunction "EPAD_57") (pintype "passive"))
      (node (ref "USB2") (pin "5") (pinfunction "5_5") (pintype "bidirectional"))
      (node (ref "USB2") (pin "P$1") (pinfunction "5_P$1") (pintype "bidirectional"))
      (node (ref "USB2") (pin "P$2") (pinfunction "5_P$2") (pintype "bidirectional"))
      (node (ref "USB2") (pin "P$3") (pinfunction "5_P$3") (pintype "bidirectional"))
      (node (ref "USB2") (pin "P$4") (pinfunction "5_P$4") (pintype "bidirectional"))
    )
    (net (code "9") (name "LED_C1") (class "Default")
      (node (ref "LED12") (pin "A") (pinfunction "A_A") (pintype "passive"))
      (node (ref "LED21") (pin "A") (pinfunction "A_A") (pintype "passive"))
      (node (ref "LED3") (pin "A") (pinfunction "A_A") (pintype "passive"))
      (node (ref "R1") (pin "2") (pinfunction "2_2") (pintype "passive"))
    )
    (net (code "10") (name "LED_C2") (class "Default")
      (node (ref "LED13") (pin "A") (pinfunction "A_A") (pintype "passive"))
      (node (ref "LED22") (pin "A") (pinfunction "A_A") (pintype "passive"))
      (node (ref "LED4") (pin "A") (pinfunction "A_A") (pintype "passive"))
      (node (ref "R8") (pin "2") (pinfunction "2_2") (pintype "passive"))
    )
    (net (code "11") (name "LED_C3") (class "Default")
      (node (ref "LED14") (pin "A") (pinfunction "A_A") (pintype "passive"))
      (node (ref "LED23") (pin "A") (pinfunction "A_A") (pintype "passive"))
      (node (ref "LED5") (pin "A") (pinfunction "A_A") (pintype "passive"))
      (node (ref "R9") (pin "2") (pinfunction "2_2") (pintype "passive"))
    )
    (net (code "12") (name "LED_C4") (class "Default")
      (node (ref "LED15") (pin "A") (pinfunction "A_A") (pintype "passive"))
      (node (ref "LED24") (pin "A") (pinfunction "A_A") (pintype "passive"))
      (node (ref "LED6") (pin "A") (pinfunction "A_A") (pintype "passive"))
      (node (ref "R10") (pin "2") (pinfunction "2_2") (pintype "passive"))
    )
    (net (code "13") (name "LED_C5") (class "Default")
      (node (ref "LED16") (pin "A") (pinfunction "A_A") (pintype "passive"))
      (node (ref "LED25") (pin "A") (pinfunction "A_A") (pintype "passive"))
      (node (ref "LED7") (pin "A") (pinfunction "A_A") (pintype "passive"))
      (node (ref "R11") (pin "2") (pinfunction "2_2") (pintype "passive"))
    )
    (net (code "14") (name "LED_C6") (class "Default")
      (node (ref "LED17") (pin "A") (pinfunction "A_A") (pintype "passive"))
      (node (ref "LED26") (pin "A") (pinfunction "A_A") (pintype "passive"))
      (node (ref "LED8") (pin "A") (pinfunction "A_A") (pintype "passive"))
      (node (ref "R12") (pin "2") (pinfunction "2_2") (pintype "passive"))
    )
    (net (code "15") (name "LED_C7") (class "Default")
      (node (ref "LED18") (pin "A") (pinfunction "A_A") (pintype "passive"))
      (node (ref "LED27") (pin "A") (pinfunction "A_A") (pintype "passive"))
      (node (ref "LED9") (pin "A") (pinfunction "A_A") (pintype "passive"))
      (node (ref "R13") (pin "2") (pinfunction "2_2") (pintype "passive"))
    )
    (net (code "16") (name "LED_C8") (class "Default")
      (node (ref "LED10") (pin "A") (pinfunction "A_A") (pintype "passive"))
      (node (ref "LED28") (pin "A") (pinfunction "A_A") (pintype "passive"))
      (node (ref "R14") (pin "2") (pinfunction "2_2") (pintype "passive"))
    )
    (net (code "17") (name "LED_C9") (class "Default")
      (node (ref "LED11") (pin "A") (pinfunction "A_A") (pintype "passive"))
      (node (ref "LED29") (pin "A") (pinfunction "A_A") (pintype "passive"))
      (node (ref "R15") (pin "2") (pinfunction "2_2") (pintype "passive"))
    )
    (net (code "18") (name "LED_INT") (class "Default")
      (node (ref "LED2") (pin "A") (pinfunction "A_A") (pintype "passive"))
      (node (ref "U2") (pin "28") (pinfunction "GPIO28_28") (pintype "bidirectional"))
    )
    (net (code "19") (name "LED_R1") (class "Default")
      (node (ref "LED10") (pin "C") (pinfunction "C_C") (pintype "passive"))
      (node (ref "LED11") (pin "C") (pinfunction "C_C") (pintype "passive"))
      (node (ref "LED3") (pin "C") (pinfunction "C_C") (pintype "passive"))
      (node (ref "LED4") (pin "C") (pinfunction "C_C") (pintype "passive"))
      (node (ref "LED5") (pin "C") (pinfunction "C_C") (pintype "passive"))
      (node (ref "LED6") (pin "C") (pinfunction "C_C") (pintype "passive"))
      (node (ref "LED7") (pin "C") (pinfunction "C_C") (pintype "passive"))
      (node (ref "LED8") (pin "C") (pinfunction "C_C") (pintype "passive"))
      (node (ref "LED9") (pin "C") (pinfunction "C_C") (pintype "passive"))
      (node (ref "R16") (pin "2") (pinfunction "2_2") (pintype "passive"))
    )
    (net (code "20") (name "LED_R2") (class "Default")
      (node (ref "LED12") (pin "C") (pinfunction "C_C") (pintype "passive"))
      (node (ref "LED13") (pin "C") (pinfunction "C_C") (pintype "passive"))
      (node (ref "LED14") (pin "C") (pinfunction "C_C") (pintype "passive"))
      (node (ref "LED15") (pin "C") (pinfunction "C_C") (pintype "passive"))
      (node (ref "LED16") (pin "C") (pinfunction "C_C") (pintype "passive"))
      (node (ref "LED17") (pin "C") (pinfunction "C_C") (pintype "passive"))
      (node (ref "LED18") (pin "C") (pinfunction "C_C") (pintype "passive"))
      (node (ref "R17") (pin "2") (pinfunction "2_2") (pintype "passive"))
    )
    (net (code "21") (name "LED_R3") (class "Default")
      (node (ref "LED21") (pin "C") (pinfunction "C_C") (pintype "passive"))
      (node (ref "LED22") (pin "C") (pinfunction "C_C") (pintype "passive"))
      (node (ref "LED23") (pin "C") (pinfunction "C_C") (pintype "passive"))
      (node (ref "LED24") (pin "C") (pinfunction "C_C") (pintype "passive"))
      (node (ref "LED25") (pin "C") (pinfunction "C_C") (pintype "passive"))
      (node (ref "LED26") (pin "C") (pinfunction "C_C") (pintype "passive"))
      (node (ref "LED27") (pin "C") (pinfunction "C_C") (pintype "passive"))
      (node (ref "LED28") (pin "C") (pinfunction "C_C") (pintype "passive"))
      (node (ref "LED29") (pin "C") (pinfunction "C_C") (pintype "passive"))
      (node (ref "R18") (pin "2") (pinfunction "2_2") (pintype "passive"))
    )
    (net (code "22") (name "Net-(BAT-2)") (class "Default")
      (node (ref "BAT") (pin "1") (pinfunction "2_1") (pintype "passive"))
      (node (ref "Q1") (pin "3") (pinfunction "D_3") (pintype "passive"))
      (node (ref "TP10") (pin "TP") (pinfunction "TP_TP") (pintype "input"))
    )
    (net (code "23") (name "Net-(C12-Pad1)") (class "Default")
      (node (ref "C12") (pin "1") (pinfunction "1_1") (pintype "passive"))
      (node (ref "C6") (pin "2") (pinfunction "2_2") (pintype "passive"))
      (node (ref "L5") (pin "1") (pinfunction "1_1") (pintype "passive"))
    )
    (net (code "24") (name "Net-(C13-Pad1)") (class "Default")
      (node (ref "C13") (pin "1") (pinfunction "1_1") (pintype "passive"))
      (node (ref "L5") (pin "2") (pinfunction "2_2") (pintype "passive"))
      (node (ref "U$2") (pin "FEED") (pinfunction "FEED_FEED") (pintype "bidirectional"))
    )
    (net (code "25") (name "Net-(C32-Pad1)") (class "Default")
      (node (ref "C32") (pin "1") (pinfunction "1_1") (pintype "passive"))
      (node (ref "R40") (pin "2") (pinfunction "2_2") (pintype "passive"))
    )
    (net (code "26") (name "Net-(D1-Pad1)") (class "Default")
      (node (ref "D1") (pin "1") (pinfunction "1_1") (pintype "bidirectional"))
      (node (ref "D1") (pin "6") (pinfunction "6_6") (pintype "bidirectional"))
      (node (ref "R47") (pin "1") (pinfunction "1_1") (pintype "passive"))
      (node (ref "TP13") (pin "TP") (pinfunction "TP_TP") (pintype "input"))
      (node (ref "USB2") (pin "3") (pinfunction "3_3") (pintype "bidirectional"))
    )
    (net (code "27") (name "Net-(D1-Pad3)") (class "Default")
      (node (ref "D1") (pin "3") (pinfunction "3_3") (pintype "bidirectional"))
      (node (ref "D1") (pin "4") (pinfunction "4_4") (pintype "bidirectional"))
      (node (ref "R46") (pin "1") (pinfunction "1_1") (pintype "passive"))
      (node (ref "TP14") (pin "TP") (pinfunction "TP_TP") (pintype "input"))
      (node (ref "USB2") (pin "2") (pinfunction "2_2") (pintype "bidirectional"))
    )
    (net (code "28") (name "Net-(F1-Pad2)") (class "Default")
      (node (ref "F1") (pin "2") (pinfunction "2_2") (pintype "passive"))
      (node (ref "P_+3V") (pin "1") (pinfunction "1_1") (pintype "bidirectional"))
    )
    (net (code "29") (name "Net-(IC1-ANT1)") (class "Default")
      (node (ref "IC1") (pin "31") (pinfunction "ANT1_31") (pintype "bidirectional"))
      (node (ref "L4") (pin "2") (pinfunction "2_2") (pintype "passive"))
      (node (ref "L6") (pin "2") (pinfunction "2_2") (pintype "passive"))
    )
    (net (code "30") (name "Net-(IC1-ANT2)") (class "Default")
      (node (ref "C6") (pin "1") (pinfunction "1_1") (pintype "passive"))
      (node (ref "IC1") (pin "32") (pinfunction "ANT2_32") (pintype "bidirectional"))
      (node (ref "L4") (pin "1") (pinfunction "1_1") (pintype "passive"))
    )
    (net (code "31") (name "Net-(IC1-DEC1)") (class "Default")
      (node (ref "C19") (pin "1") (pinfunction "1_1") (pintype "passive"))
      (node (ref "IC1") (pin "39") (pinfunction "DEC1_39") (pintype "bidirectional"))
    )
    (net (code "32") (name "Net-(IC1-DEC2)") (class "Default")
      (node (ref "C10") (pin "1") (pinfunction "1_1") (pintype "passive"))
      (node (ref "IC1") (pin "29") (pinfunction "DEC2_29") (pintype "bidirectional"))
    )
    (net (code "33") (name "Net-(IC1-VDD_PA)") (class "Default")
      (node (ref "C14") (pin "1") (pinfunction "1_1") (pintype "passive"))
      (node (ref "IC1") (pin "30") (pinfunction "VDD_PA_30") (pintype "bidirectional"))
      (node (ref "L6") (pin "1") (pinfunction "1_1") (pintype "passive"))
    )
    (net (code "34") (name "Net-(IC1-XC1)") (class "Default")
      (node (ref "C23") (pin "1") (pinfunction "1_1") (pintype "passive"))
      (node (ref "IC1") (pin "37") (pinfunction "XC1_37") (pintype "bidirectional"))
      (node (ref "Q2") (pin "1") (pinfunction "X1_1") (pintype "bidirectional"))
    )
    (net (code "35") (name "Net-(IC1-XC2)") (class "Default")
      (node (ref "C25") (pin "1") (pinfunction "1_1") (pintype "passive"))
      (node (ref "IC1") (pin "38") (pinfunction "XC2_38") (pintype "bidirectional"))
      (node (ref "Q2") (pin "3") (pinfunction "X2_3") (pintype "bidirectional"))
    )
    (net (code "36") (name "Net-(IC3-OUT1)") (class "Default")
      (node (ref "IC3") (pin "2") (pinfunction "OUT1_2") (pintype "bidirectional"))
      (node (ref "JP1") (pin "3") (pinfunction "3_3") (pintype "passive"))
      (node (ref "R4") (pin "1") (pinfunction "1_1") (pintype "passive"))
    )
    (net (code "37") (name "Net-(IC3-OUT2)") (class "Default")
      (node (ref "IC3") (pin "3") (pinfunction "OUT2_3") (pintype "bidirectional"))
      (node (ref "JP1") (pin "2") (pinfunction "2_2") (pintype "passive"))
      (node (ref "SPK1") (pin "-LEAD") (pinfunction "1_-LEAD") (pintype "passive"))
    )
    (net (code "38") (name "Net-(IC5A-+IN)") (class "Default")
      (node (ref "C33") (pin "1") (pinfunction "1_1") (pintype "passive"))
      (node (ref "IC5") (pin "3") (pinfunction "+IN_3") (pintype "input"))
      (node (ref "R42") (pin "1") (pinfunction "1_1") (pintype "passive"))
      (node (ref "R43") (pin "2") (pinfunction "2_2") (pintype "passive"))
    )
    (net (code "39") (name "Net-(IC5A--IN)") (class "Default")
      (node (ref "IC5") (pin "4") (pinfunction "-IN_4") (pintype "input"))
      (node (ref "R40") (pin "1") (pinfunction "1_1") (pintype "passive"))
      (node (ref "R41") (pin "2") (pinfunction "2_2") (pintype "passive"))
    )
    (net (code "40") (name "Net-(L2-Pad1)") (class "Default")
      (node (ref "L2") (pin "1") (pinfunction "1_1") (pintype "passive"))
      (node (ref "USB2") (pin "1") (pinfunction "1_1") (pintype "bidirectional"))
    )
    (net (code "41") (name "Net-(LED2-PadC)") (class "Default")
      (node (ref "LED2") (pin "C") (pinfunction "C_C") (pintype "passive"))
      (node (ref "R34") (pin "1") (pinfunction "1_1") (pintype "passive"))
    )
    (net (code "42") (name "Net-(MIC1-OUT)") (class "Default")
      (node (ref "C32") (pin "2") (pinfunction "2_2") (pintype "passive"))
      (node (ref "MIC1") (pin "4") (pinfunction "OUT_4") (pintype "bidirectional"))
    )
    (net (code "43") (name "Net-(Q1-G)") (class "Default")
      (node (ref "Q1") (pin "1") (pinfunction "G_1") (pintype "passive"))
      (node (ref "R49") (pin "2") (pinfunction "2_2") (pintype "passive"))
      (node (ref "R5") (pin "2") (pinfunction "2_2") (pintype "passive"))
    )
    (net (code "44") (name "Net-(Q3-X2)") (class "Default")
      (node (ref "C22") (pin "1") (pinfunction "1_1") (pintype "passive"))
      (node (ref "Q3") (pin "3") (pinfunction "X2_3") (pintype "bidirectional"))
      (node (ref "R50") (pin "1") (pinfunction "1_1") (pintype "passive"))
    )
    (net (code "45") (name "Net-(Q4-G)") (class "Default")
      (node (ref "Q4") (pin "1") (pinfunction "G_1") (pintype "passive"))
      (node (ref "R21") (pin "2") (pinfunction "2_2") (pintype "passive"))
    )
    (net (code "46") (name "Net-(SPK1-2)") (class "Default")
      (node (ref "R4") (pin "2") (pinfunction "2_2") (pintype "passive"))
      (node (ref "SPK1") (pin "+LEAD") (pinfunction "2_+LEAD") (pintype "passive"))
    )
    (net (code "47") (name "Net-(TAST_RESET-S)") (class "Default")
      (node (ref "R22") (pin "1") (pinfunction "1_1") (pintype "passive"))
      (node (ref "TAST_RESET") (pin "3") (pinfunction "S_3") (pintype "passive"))
      (node (ref "TAST_RESET") (pin "4") (pinfunction "S1_4") (pintype "passive"))
    )
    (net (code "48") (name "Net-(U1-DRDYM)") (class "Default")
      (node (ref "R31") (pin "1") (pinfunction "1_1") (pintype "passive"))
      (node (ref "U1") (pin "2") (pinfunction "DRDYM_2") (pintype "bidirectional"))
    )
    (net (code "49") (name "Net-(U1-INT1)") (class "Default")
      (node (ref "R29") (pin "2") (pinfunction "2_2") (pintype "passive"))
      (node (ref "U1") (pin "19") (pinfunction "INT1_19") (pintype "bidirectional"))
    )
    (net (code "50") (name "Net-(U1-INT3)") (class "Default")
      (node (ref "R32") (pin "2") (pinfunction "2_2") (pintype "passive"))
      (node (ref "U1") (pin "14") (pinfunction "INT3_14") (pintype "bidirectional"))
    )
    (net (code "51") (name "P0") (class "Default")
      (node (ref "EXP1") (pin "24") (pinfunction "S_24") (pintype "passive"))
      (node (ref "IC1") (pin "4") (pinfunction "P0.00_4") (pintype "bidirectional"))
      (node (ref "P_0") (pin "1") (pinfunction "1_1") (pintype "bidirectional"))
      (node (ref "R6") (pin "1") (pinfunction "1_1") (pintype "passive"))
    )
    (net (code "52") (name "P1") (class "Default")
      (node (ref "EXP1") (pin "23") (pinfunction "S_23") (pintype "passive"))
      (node (ref "IC1") (pin "5") (pinfunction "P0.01_5") (pintype "bidirectional"))
      (node (ref "P_1") (pin "1") (pinfunction "1_1") (pintype "bidirectional"))
      (node (ref "R7") (pin "1") (pinfunction "1_1") (pintype "passive"))
    )
    (net (code "53") (name "P2") (class "Default")
      (node (ref "EXP1") (pin "22") (pinfunction "S_22") (pintype "passive"))
      (node (ref "IC1") (pin "6") (pinfunction "P0.02_6") (pintype "bidirectional"))
      (node (ref "P_2") (pin "1") (pinfunction "1_1") (pintype "bidirectional"))
      (node (ref "R19") (pin "1") (pinfunction "1_1") (pintype "passive"))
    )
    (net (code "54") (name "P3") (class "Default")
      (node (ref "C34") (pin "1") (pinfunction "1_1") (pintype "passive"))
      (node (ref "IC1") (pin "7") (pinfunction "P0.03_7") (pintype "bidirectional"))
      (node (ref "IC5") (pin "1") (pinfunction "OUT_1") (pintype "output"))
      (node (ref "R41") (pin "1") (pinfunction "1_1") (pintype "passive"))
    )
    (net (code "55") (name "P4") (class "Default")
      (node (ref "EXP1") (pin "20") (pinfunction "S_20") (pintype "passive"))
      (node (ref "IC1") (pin "8") (pinfunction "P0.04_8") (pintype "bidirectional"))
      (node (ref "R1") (pin "1") (pinfunction "1_1") (pintype "passive"))
    )
    (net (code "56") (name "P5") (class "Default")
      (node (ref "EXP1") (pin "19") (pinfunction "S_19") (pintype "passive"))
      (node (ref "IC1") (pin "9") (pinfunction "P0.05_9") (pintype "bidirectional"))
      (node (ref "R8") (pin "1") (pinfunction "1_1") (pintype "passive"))
    )
    (net (code "57") (name "P6") (class "Default")
      (node (ref "EXP1") (pin "18") (pinfunction "S_18") (pintype "passive"))
      (node (ref "IC1") (pin "10") (pinfunction "P0.06_10") (pintype "bidirectional"))
      (node (ref "R9") (pin "1") (pinfunction "1_1") (pintype "passive"))
    )
    (net (code "58") (name "P7") (class "Default")
      (node (ref "EXP1") (pin "17") (pinfunction "S_17") (pintype "passive"))
      (node (ref "IC1") (pin "11") (pinfunction "P0.07_11") (pintype "bidirectional"))
      (node (ref "R10") (pin "1") (pinfunction "1_1") (pintype "passive"))
    )
    (net (code "59") (name "P8") (class "Default")
      (node (ref "EXP1") (pin "16") (pinfunction "S_16") (pintype "passive"))
      (node (ref "IC1") (pin "14") (pinfunction "P0.08_14") (pintype "bidirectional"))
      (node (ref "R11") (pin "1") (pinfunction "1_1") (pintype "passive"))
    )
    (net (code "60") (name "P9") (class "Default")
      (node (ref "EXP1") (pin "15") (pinfunction "S_15") (pintype "passive"))
      (node (ref "IC1") (pin "15") (pinfunction "P0.09_15") (pintype "bidirectional"))
      (node (ref "R12") (pin "1") (pinfunction "1_1") (pintype "passive"))
    )
    (net (code "61") (name "P10") (class "Default")
      (node (ref "EXP1") (pin "12") (pinfunction "S_12") (pintype "passive"))
      (node (ref "IC1") (pin "16") (pinfunction "P0.10_16") (pintype "bidirectional"))
      (node (ref "R13") (pin "1") (pinfunction "1_1") (pintype "passive"))
    )
    (net (code "62") (name "P11") (class "Default")
      (node (ref "EXP1") (pin "11") (pinfunction "S_11") (pintype "passive"))
      (node (ref "IC1") (pin "17") (pinfunction "P0.11_17") (pintype "bidirectional"))
      (node (ref "R14") (pin "1") (pinfunction "1_1") (pintype "passive"))
    )
    (net (code "63") (name "P12") (class "Default")
      (node (ref "EXP1") (pin "10") (pinfunction "S_10") (pintype "passive"))
      (node (ref "IC1") (pin "18") (pinfunction "P0.12_18") (pintype "bidirectional"))
      (node (ref "R15") (pin "1") (pinfunction "1_1") (pintype "passive"))
    )
    (net (code "64") (name "P13") (class "Default")
      (node (ref "EXP1") (pin "9") (pinfunction "S_9") (pintype "passive"))
      (node (ref "IC1") (pin "19") (pinfunction "P0.13_19") (pintype "bidirectional"))
      (node (ref "R16") (pin "1") (pinfunction "1_1") (pintype "passive"))
    )
    (net (code "65") (name "P14") (class "Default")
      (node (ref "EXP1") (pin "8") (pinfunction "S_8") (pintype "passive"))
      (node (ref "IC1") (pin "20") (pinfunction "P0.14_20") (pintype "bidirectional"))
      (node (ref "R17") (pin "1") (pinfunction "1_1") (pintype "passive"))
    )
    (net (code "66") (name "P15") (class "Default")
      (node (ref "EXP1") (pin "7") (pinfunction "S_7") (pintype "passive"))
      (node (ref "IC1") (pin "21") (pinfunction "P0.15_21") (pintype "bidirectional"))
      (node (ref "R18") (pin "1") (pinfunction "1_1") (pintype "passive"))
    )
    (net (code "67") (name "P16") (class "Default")
      (node (ref "IC1") (pin "22") (pinfunction "P0.16_22") (pintype "bidirectional"))
      (node (ref "R2") (pin "1") (pinfunction "1_1") (pintype "passive"))
      (node (ref "TAST_B") (pin "3") (pinfunction "S1_3") (pintype "passive"))
      (node (ref "TAST_B") (pin "4") (pinfunction "S2_4") (pintype "passive"))
    )
    (net (code "68") (name "P17") (class "Default")
      (node (ref "IC1") (pin "25") (pinfunction "P0.17_25") (pintype "bidirectional"))
      (node (ref "R3") (pin "1") (pinfunction "1_1") (pintype "passive"))
      (node (ref "TAST_A") (pin "3") (pinfunction "S1_3") (pintype "passive"))
      (node (ref "TAST_A") (pin "4") (pinfunction "S2_4") (pintype "passive"))
    )
    (net (code "69") (name "P18") (class "Default")
      (node (ref "IC1") (pin "26") (pinfunction "P0.18_26") (pintype "bidirectional"))
      (node (ref "LED1") (pin "1") (pinfunction "DI_1") (pintype "input"))
    )
    (net (code "70") (name "P19") (class "Default")
      (node (ref "IC1") (pin "27") (pinfunction "P0.19_27") (pintype "bidirectional"))
      (node (ref "R24") (pin "1") (pinfunction "1_1") (pintype "passive"))
    )
    (net (code "71") (name "P20") (class "Default")
      (node (ref "IC1") (pin "28") (pinfunction "P0.20_28") (pintype "bidirectional"))
      (node (ref "R23") (pin "1") (pinfunction "1_1") (pintype "passive"))
    )
    (net (code "72") (name "P21") (class "Default")
      (node (ref "IC1") (pin "40") (pinfunction "P0.21_40") (pintype "bidirectional"))
      (node (ref "R29") (pin "1") (pinfunction "1_1") (pintype "passive"))
      (node (ref "R30") (pin "1") (pinfunction "1_1") (pintype "passive"))
      (node (ref "R32") (pin "1") (pinfunction "1_1") (pintype "passive"))
    )
    (net (code "73") (name "P22") (class "Default")
      (node (ref "EXP1") (pin "21") (pinfunction "S_21") (pintype "passive"))
      (node (ref "IC1") (pin "41") (pinfunction "P0.22_41") (pintype "bidirectional"))
      (node (ref "P_3") (pin "1") (pinfunction "1_1") (pintype "bidirectional"))
      (node (ref "R20") (pin "1") (pinfunction "1_1") (pintype "passive"))
    )
    (net (code "74") (name "P23") (class "Default")
      (node (ref "IC1") (pin "42") (pinfunction "P0.23_42") (pintype "bidirectional"))
      (node (ref "R31") (pin "2") (pinfunction "2_2") (pintype "passive"))
      (node (ref "R48") (pin "1") (pinfunction "1_1") (pintype "passive"))
    )
    (net (code "75") (name "P24") (class "Default")
      (node (ref "IC1") (pin "43") (pinfunction "P0.24_43") (pintype "bidirectional"))
      (node (ref "R39") (pin "2") (pinfunction "2_2") (pintype "passive"))
    )
    (net (code "76") (name "P25") (class "Default")
      (node (ref "IC1") (pin "44") (pinfunction "P0.25_44") (pintype "bidirectional"))
      (node (ref "R38") (pin "2") (pinfunction "2_2") (pintype "passive"))
    )
    (net (code "77") (name "P26") (class "Default")
      (node (ref "C42") (pin "1") (pinfunction "1_1") (pintype "passive"))
      (node (ref "EXP1") (pin "6") (pinfunction "S_6") (pintype "passive"))
      (node (ref "IC1") (pin "45") (pinfunction "P0.26_45") (pintype "bidirectional"))
      (node (ref "R27") (pin "1") (pinfunction "1_1") (pintype "passive"))
    )
    (net (code "78") (name "P27") (class "Default")
      (node (ref "C41") (pin "1") (pinfunction "1_1") (pintype "passive"))
      (node (ref "EXP1") (pin "5") (pinfunction "S_5") (pintype "passive"))
      (node (ref "IC1") (pin "46") (pinfunction "P0.27_46") (pintype "bidirectional"))
      (node (ref "R28") (pin "1") (pinfunction "1_1") (pintype "passive"))
    )
    (net (code "79") (name "P28") (class "Default")
      (node (ref "IC1") (pin "47") (pinfunction "P0.28_47") (pintype "bidirectional"))
      (node (ref "IC3") (pin "7") (pinfunction "SLEEP_7") (pintype "bidirectional"))
    )
    (net (code "80") (name "P29") (class "Default")
      (node (ref "IC1") (pin "48") (pinfunction "P0.29_48") (pintype "bidirectional"))
      (node (ref "IC3") (pin "6") (pinfunction "IN1_6") (pintype "bidirectional"))
    )
    (net (code "81") (name "P30") (class "Default")
      (node (ref "IC1") (pin "3") (pinfunction "P0.30_3") (pintype "bidirectional"))
      (node (ref "IC3") (pin "5") (pinfunction "IN2_5") (pintype "bidirectional"))
    )
    (net (code "82") (name "RX") (class "Default")
      (node (ref "R27") (pin "2") (pinfunction "2_2") (pintype "passive"))
      (node (ref "SERIAL") (pin "1") (pinfunction "1_1") (pintype "bidirectional"))
    )
    (net (code "83") (name "RX_TAR") (class "Default")
      (node (ref "R39") (pin "1") (pinfunction "1_1") (pintype "passive"))
      (node (ref "TP6") (pin "TP") (pinfunction "TP_TP") (pintype "input"))
      (node (ref "U2") (pin "29") (pinfunction "GPIO18_29") (pintype "bidirectional"))
    )
    (net (code "84") (name "SCL{slash}P19") (class "Default")
      (node (ref "EXP1") (pin "3") (pinfunction "S_3") (pintype "passive"))
      (node (ref "I2C") (pin "1") (pinfunction "1_1") (pintype "bidirectional"))
      (node (ref "R24") (pin "2") (pinfunction "2_2") (pintype "passive"))
      (node (ref "R26") (pin "1") (pinfunction "1_1") (pintype "passive"))
      (node (ref "U1") (pin "9") (pinfunction "SCX_9") (pintype "bidirectional"))
    )
    (net (code "85") (name "SDA{slash}P20") (class "Default")
      (node (ref "EXP1") (pin "4") (pinfunction "S_4") (pintype "passive"))
      (node (ref "I2C") (pin "2") (pinfunction "2_2") (pintype "bidirectional"))
      (node (ref "R23") (pin "2") (pinfunction "2_2") (pintype "passive"))
      (node (ref "R25") (pin "1") (pinfunction "1_1") (pintype "passive"))
      (node (ref "U1") (pin "11") (pinfunction "SDX_11") (pintype "bidirectional"))
    )
    (net (code "86") (name "SWCLK_INT") (class "Default")
      (node (ref "TP1") (pin "TP") (pinfunction "TP_TP") (pintype "input"))
      (node (ref "U2") (pin "24") (pinfunction "SWCLK_24") (pintype "passive"))
    )
    (net (code "87") (name "SWDCLK_TAR") (class "Default")
      (node (ref "IC1") (pin "24") (pinfunction "SWDCLK_24") (pintype "bidirectional"))
      (node (ref "TP7") (pin "TP") (pinfunction "TP_TP") (pintype "input"))
      (node (ref "U2") (pin "14") (pinfunction "GPIO11_14") (pintype "bidirectional"))
    )
    (net (code "88") (name "SWDIO_INT") (class "Default")
      (node (ref "TP4") (pin "TP") (pinfunction "TP_TP") (pintype "input"))
      (node (ref "U2") (pin "25") (pinfunction "SWDIO_25") (pintype "bidirectional"))
    )
    (net (code "89") (name "SWDIO_TAR") (class "Default")
      (node (ref "IC1") (pin "23") (pinfunction "SWDIO/NRESET_23") (pintype "bidirectional"))
      (node (ref "R37") (pin "1") (pinfunction "1_1") (pintype "passive"))
      (node (ref "TP8") (pin "TP") (pinfunction "TP_TP") (pintype "input"))
      (node (ref "U2") (pin "13") (pinfunction "GPIO10_13") (pintype "bidirectional"))
    )
    (net (code "90") (name "TX") (class "Default")
      (node (ref "R28") (pin "2") (pinfunction "2_2") (pintype "passive"))
      (node (ref "SERIAL") (pin "2") (pinfunction "2_2") (pintype "bidirectional"))
    )
    (net (code "91") (name "TX_TAR") (class "Default")
      (node (ref "R38") (pin "1") (pinfunction "1_1") (pintype "passive"))
      (node (ref "TP9") (pin "TP") (pinfunction "TP_TP") (pintype "input"))
      (node (ref "U2") (pin "30") (pinfunction "GPIO19_30") (pintype "bidirectional"))
    )
    (net (code "92") (name "USB_DM") (class "Default")
      (node (ref "R46") (pin "2") (pinfunction "2_2") (pintype "passive"))
      (node (ref "U2") (pin "46") (pinfunction "USB_DM_46") (pintype "passive"))
    )
    (net (code "93") (name "USB_DP") (class "Default")
      (node (ref "R47") (pin "2") (pinfunction "2_2") (pintype "passive"))
      (node (ref "U2") (pin "47") (pinfunction "USB_DP_47") (pintype "passive"))
    )
    (net (code "94") (name "USB_VREG") (class "Default")
      (node (ref "C4") (pin "1") (pinfunction "1_1") (pintype "passive"))
      (node (ref "IC2") (pin "5") (pinfunction "OUT_5") (pintype "output"))
      (node (ref "Q4") (pin "3") (pinfunction "D_3") (pintype "passive"))
      (node (ref "TP5") (pin "TP") (pinfunction "TP_TP") (pintype "input"))
    )
    (net (code "95") (name "VCC") (class "Default")
      (node (ref "C1") (pin "1") (pinfunction "1_1") (pintype "passive"))
      (node (ref "C15") (pin "1") (pinfunction "1_1") (pintype "passive"))
      (node (ref "C17") (pin "1") (pinfunction "1_1") (pintype "passive"))
      (node (ref "C18") (pin "1") (pinfunction "1_1") (pintype "passive"))
      (node (ref "C2") (pin "1") (pinfunction "1_1") (pintype "passive"))
      (node (ref "C24") (pin "1") (pinfunction "1_1") (pintype "passive"))
      (node (ref "C29") (pin "1") (pinfunction "1_1") (pintype "passive"))
      (node (ref "C3") (pin "+") (pinfunction "+_+") (pintype "passive"))
      (node (ref "C30") (pin "1") (pinfunction "1_1") (pintype "passive"))
      (node (ref "C31") (pin "1") (pinfunction "1_1") (pintype "passive"))
      (node (ref "C35") (pin "1") (pinfunction "1_1") (pintype "passive"))
      (node (ref "C36") (pin "1") (pinfunction "1_1") (pintype "passive"))
      (node (ref "C37") (pin "1") (pinfunction "1_1") (pintype "passive"))
      (node (ref "C38") (pin "1") (pinfunction "1_1") (pintype "passive"))
      (node (ref "C45") (pin "1") (pinfunction "1_1") (pintype "passive"))
      (node (ref "C46") (pin "1") (pinfunction "1_1") (pintype "passive"))
      (node (ref "C47") (pin "1") (pinfunction "1_1") (pintype "passive"))
      (node (ref "C48") (pin "1") (pinfunction "1_1") (pintype "passive"))
      (node (ref "C49") (pin "1") (pinfunction "1_1") (pintype "passive"))
      (node (ref "C5") (pin "1") (pinfunction "1_1") (pintype "passive"))
      (node (ref "C50") (pin "1") (pinfunction "1_1") (pintype "passive"))
      (node (ref "C51") (pin "1") (pinfunction "1_1") (pintype "passive"))
      (node (ref "C7") (pin "1") (pinfunction "1_1") (pintype "passive"))
      (node (ref "C8") (pin "1") (pinfunction "1_1") (pintype "passive"))
      (node (ref "C9") (pin "1") (pinfunction "1_1") (pintype "passive"))
      (node (ref "D3") (pin "A") (pinfunction "A_A") (pintype "passive"))
      (node (ref "EXP1") (pin "2") (pinfunction "S_2") (pintype "passive"))
      (node (ref "EXP1") (pin "25") (pinfunction "S_25") (pintype "passive"))
      (node (ref "F1") (pin "1") (pinfunction "1_1") (pintype "passive"))
      (node (ref "I2C") (pin "3") (pinfunction "3_3") (pintype "bidirectional"))
      (node (ref "IC1") (pin "1") (pinfunction "VDD_1") (pintype "bidirectional"))
      (node (ref "IC1") (pin "12") (pinfunction "VDD_2_12") (pintype "bidirectional"))
      (node (ref "IC1") (pin "35") (pinfunction "AVDD_35") (pintype "bidirectional"))
      (node (ref "IC1") (pin "36") (pinfunction "AVDD_2_36") (pintype "bidirectional"))
      (node (ref "IC3") (pin "8") (pinfunction "VCC_8") (pintype "bidirectional"))
      (node (ref "IC5") (pin "5") (pinfunction "V+_5") (pintype "power_in"))
      (node (ref "IC6") (pin "8") (pinfunction "VCC_8") (pintype "bidirectional"))
      (node (ref "LED1") (pin "2") (pinfunction "VDD_2") (pintype "power_in"))
      (node (ref "MIC1") (pin "1") (pinfunction "VDD_1") (pintype "bidirectional"))
      (node (ref "Q1") (pin "2") (pinfunction "S_2") (pintype "passive"))
      (node (ref "Q4") (pin "2") (pinfunction "S_2") (pintype "passive"))
      (node (ref "R19") (pin "2") (pinfunction "2_2") (pintype "passive"))
      (node (ref "R2") (pin "2") (pinfunction "2_2") (pintype "passive"))
      (node (ref "R20") (pin "2") (pinfunction "2_2") (pintype "passive"))
      (node (ref "R25") (pin "2") (pinfunction "2_2") (pintype "passive"))
      (node (ref "R26") (pin "2") (pinfunction "2_2") (pintype "passive"))
      (node (ref "R3") (pin "2") (pinfunction "2_2") (pintype "passive"))
      (node (ref "R30") (pin "2") (pinfunction "2_2") (pintype "passive"))
      (node (ref "R34") (pin "2") (pinfunction "2_2") (pintype "passive"))
      (node (ref "R37") (pin "2") (pinfunction "2_2") (pintype "passive"))
      (node (ref "R42") (pin "2") (pinfunction "2_2") (pintype "passive"))
      (node (ref "R45") (pin "2") (pinfunction "2_2") (pintype "passive"))
      (node (ref "R48") (pin "2") (pinfunction "2_2") (pintype "passive"))
      (node (ref "R6") (pin "2") (pinfunction "2_2") (pintype "passive"))
      (node (ref "R7") (pin "2") (pinfunction "2_2") (pintype "passive"))
      (node (ref "SERIAL") (pin "3") (pinfunction "3_3") (pintype "bidirectional"))
      (node (ref "U1") (pin "13") (pinfunction "VDDIO_13") (pintype "bidirectional"))
      (node (ref "U1") (pin "3") (pinfunction "VDD_3") (pintype "bidirectional"))
      (node (ref "U1") (pin "7") (pinfunction "PS_7") (pintype "bidirectional"))
      (node (ref "U2") (pin "1") (pinfunction "IOVDD_2_1") (pintype "power_in"))
      (node (ref "U2") (pin "10") (pinfunction "IOVDD_3_10") (pintype "power_in"))
      (node (ref "U2") (pin "22") (pinfunction "IOVDD_4_22") (pintype "power_in"))
      (node (ref "U2") (pin "26") (pinfunction "RUN_26") (pintype "passive"))
      (node (ref "U2") (pin "33") (pinfunction "IOVDD_5_33") (pintype "power_in"))
      (node (ref "U2") (pin "42") (pinfunction "IOVDD_6_42") (pintype "power_in"))
      (node (ref "U2") (pin "43") (pinfunction "ADC_AVDD_43") (pintype "power_in"))
      (node (ref "U2") (pin "44") (pinfunction "VREG_VIN_44") (pintype "power_in"))
      (node (ref "U2") (pin "48") (pinfunction "USB_VDD_48") (pintype "power_in"))
      (node (ref "U2") (pin "49") (pinfunction "IOVDD_49") (pintype "power_in"))
    )
    (net (code "96") (name "VM") (class "Default")
      (node (ref "C16") (pin "1") (pinfunction "1_1") (pintype "passive"))
      (node (ref "C26") (pin "1") (pinfunction "1_1") (pintype "passive"))
      (node (ref "D3") (pin "C") (pinfunction "C_C") (pintype "passive"))
      (node (ref "IC3") (pin "1") (pinfunction "VM_1") (pintype "bidirectional"))
      (node (ref "JP1") (pin "5") (pinfunction "5_5") (pintype "passive"))
    )
    (net (code "97") (name "VREG_VOUT") (class "Default")
      (node (ref "C43") (pin "1") (pinfunction "1_1") (pintype "passive"))
      (node (ref "C44") (pin "1") (pinfunction "1_1") (pintype "passive"))
      (node (ref "C52") (pin "1") (pinfunction "1_1") (pintype "passive"))
      (node (ref "U2") (pin "23") (pinfunction "DVDD_2_23") (pintype "power_in"))
      (node (ref "U2") (pin "45") (pinfunction "VREG_VOUT_45") (pintype "power_in"))
      (node (ref "U2") (pin "50") (pinfunction "DVDD_50") (pintype "power_in"))
    )
    (net (code "98") (name "XIN") (class "Default")
      (node (ref "C21") (pin "1") (pinfunction "1_1") (pintype "passive"))
      (node (ref "Q3") (pin "1") (pinfunction "X1_1") (pintype "bidirectional"))
      (node (ref "U2") (pin "20") (pinfunction "XIN_20") (pintype "input"))
    )
    (net (code "99") (name "XOUT") (class "Default")
      (node (ref "R50") (pin "2") (pinfunction "2_2") (pintype "passive"))
      (node (ref "U2") (pin "21") (pinfunction "XOUT_21") (pintype "output"))
    )
    (net (code "100") (name "unconnected-(IC1-DCC-Pad2)") (class "Default")
      (node (ref "IC1") (pin "2") (pinfunction "DCC_2") (pintype "bidirectional"))
    )
    (net (code "101") (name "unconnected-(IC2-NC-Pad4)") (class "Default")
      (node (ref "IC2") (pin "4") (pinfunction "NC_4") (pintype "no_connect"))
    )
    (net (code "102") (name "unconnected-(LED1-DO-Pad3)") (class "Default")
      (node (ref "LED1") (pin "3") (pinfunction "DO_3") (pintype "output"))
    )
    (net (code "103") (name "unconnected-(U1-CSB1-Pad16)") (class "Default")
      (node (ref "U1") (pin "16") (pinfunction "CSB1_16") (pintype "bidirectional"))
    )
    (net (code "104") (name "unconnected-(U1-CSB2-Pad5)") (class "Default")
      (node (ref "U1") (pin "5") (pinfunction "CSB2_5") (pintype "bidirectional"))
    )
    (net (code "105") (name "unconnected-(U1-INT2-Pad1)") (class "Default")
      (node (ref "U1") (pin "1") (pinfunction "INT2_1") (pintype "bidirectional"))
    )
    (net (code "106") (name "unconnected-(U1-INT4-Pad15)") (class "Default")
      (node (ref "U1") (pin "15") (pinfunction "INT4_15") (pintype "bidirectional"))
    )
    (net (code "107") (name "unconnected-(U1-INT5-Pad10)") (class "Default")
      (node (ref "U1") (pin "10") (pinfunction "INT5_10") (pintype "bidirectional"))
    )
    (net (code "108") (name "unconnected-(U1-N{slash}C-Pad8)") (class "Default")
      (node (ref "U1") (pin "8") (pinfunction "N/C_8") (pintype "bidirectional"))
    )
    (net (code "109") (name "unconnected-(U1-N{slash}C-Pad18)") (class "Default")
      (node (ref "U1") (pin "18") (pinfunction "N/C_18") (pintype "bidirectional"))
    )
    (net (code "110") (name "unconnected-(U2-GPIO0-Pad2)") (class "Default")
      (node (ref "U2") (pin "2") (pinfunction "GPIO0_2") (pintype "bidirectional"))
    )
    (net (code "111") (name "unconnected-(U2-GPIO1-Pad3)") (class "Default")
      (node (ref "U2") (pin "3") (pinfunction "GPIO1_3") (pintype "bidirectional"))
    )
    (net (code "112") (name "unconnected-(U2-GPIO2-Pad4)") (class "Default")
      (node (ref "U2") (pin "4") (pinfunction "GPIO2_4") (pintype "bidirectional"))
    )
    (net (code "113") (name "unconnected-(U2-GPIO3-Pad5)") (class "Default")
      (node (ref "U2") (pin "5") (pinfunction "GPIO3_5") (pintype "bidirectional"))
    )
    (net (code "114") (name "unconnected-(U2-GPIO4-Pad6)") (class "Default")
      (node (ref "U2") (pin "6") (pinfunction "GPIO4_6") (pintype "bidirectional"))
    )
    (net (code "115") (name "unconnected-(U2-GPIO5-Pad7)") (class "Default")
      (node (ref "U2") (pin "7") (pinfunction "GPIO5_7") (pintype "bidirectional"))
    )
    (net (code "116") (name "unconnected-(U2-GPIO6-Pad8)") (class "Default")
      (node (ref "U2") (pin "8") (pinfunction "GPIO6_8") (pintype "bidirectional"))
    )
    (net (code "117") (name "unconnected-(U2-GPIO7-Pad9)") (class "Default")
      (node (ref "U2") (pin "9") (pinfunction "GPIO7_9") (pintype "bidirectional"))
    )
    (net (code "118") (name "unconnected-(U2-GPIO8-Pad11)") (class "Default")
      (node (ref "U2") (pin "11") (pinfunction "GPIO8_11") (pintype "bidirectional"))
    )
    (net (code "119") (name "unconnected-(U2-GPIO9-Pad12)") (class "Default")
      (node (ref "U2") (pin "12") (pinfunction "GPIO9_12") (pintype "bidirectional"))
    )
    (net (code "120") (name "unconnected-(U2-GPIO12-Pad15)") (class "Default")
      (node (ref "U2") (pin "15") (pinfunction "GPIO12_15") (pintype "bidirectional"))
    )
    (net (code "121") (name "unconnected-(U2-GPIO13-Pad16)") (class "Default")
      (node (ref "U2") (pin "16") (pinfunction "GPIO13_16") (pintype "bidirectional"))
    )
    (net (code "122") (name "unconnected-(U2-GPIO14-Pad17)") (class "Default")
      (node (ref "U2") (pin "17") (pinfunction "GPIO14_17") (pintype "bidirectional"))
    )
    (net (code "123") (name "unconnected-(U2-GPIO15-Pad18)") (class "Default")
      (node (ref "U2") (pin "18") (pinfunction "GPIO15_18") (pintype "bidirectional"))
    )
    (net (code "124") (name "unconnected-(U2-GPIO16-Pad27)") (class "Default")
      (node (ref "U2") (pin "27") (pinfunction "GPIO16_27") (pintype "bidirectional"))
    )
    (net (code "125") (name "unconnected-(U2-GPIO20-Pad31)") (class "Default")
      (node (ref "U2") (pin "31") (pinfunction "GPIO20_31") (pintype "bidirectional"))
    )
    (net (code "126") (name "unconnected-(U2-GPIO21-Pad32)") (class "Default")
      (node (ref "U2") (pin "32") (pinfunction "GPIO21_32") (pintype "bidirectional"))
    )
    (net (code "127") (name "unconnected-(U2-GPIO22-Pad34)") (class "Default")
      (node (ref "U2") (pin "34") (pinfunction "GPIO22_34") (pintype "bidirectional"))
    )
    (net (code "128") (name "unconnected-(U2-GPIO23-Pad35)") (class "Default")
      (node (ref "U2") (pin "35") (pinfunction "GPIO23_35") (pintype "bidirectional"))
    )
    (net (code "129") (name "unconnected-(U2-GPIO24-Pad36)") (class "Default")
      (node (ref "U2") (pin "36") (pinfunction "GPIO24_36") (pintype "bidirectional"))
    )
    (net (code "130") (name "unconnected-(U2-GPIO25-Pad37)") (class "Default")
      (node (ref "U2") (pin "37") (pinfunction "GPIO25_37") (pintype "bidirectional"))
    )
    (net (code "131") (name "unconnected-(U2-GPIO26{slash}ADC0-Pad38)") (class "Default")
      (node (ref "U2") (pin "38") (pinfunction "GPIO26/ADC0_38") (pintype "bidirectional"))
    )
    (net (code "132") (name "unconnected-(U2-GPIO27{slash}ADC1-Pad39)") (class "Default")
      (node (ref "U2") (pin "39") (pinfunction "GPIO27/ADC1_39") (pintype "bidirectional"))
    )
    (net (code "133") (name "unconnected-(U2-GPIO28{slash}ADC2-Pad40)") (class "Default")
      (node (ref "U2") (pin "40") (pinfunction "GPIO28/ADC2_40") (pintype "bidirectional"))
    )
    (net (code "134") (name "unconnected-(U2-GPIO29{slash}SDC3-Pad41)") (class "Default")
      (node (ref "U2") (pin "41") (pinfunction "GPIO29/SDC3_41") (pintype "bidirectional"))
    )
    (net (code "135") (name "unconnected-(USB2-Pad4)") (class "Default")
      (node (ref "USB2") (pin "4") (pinfunction "4_4") (pintype "bidirectional"))
    )
  )
)
